# IN14.net
KiCad netlist of a schematic drawn in Altium Designer
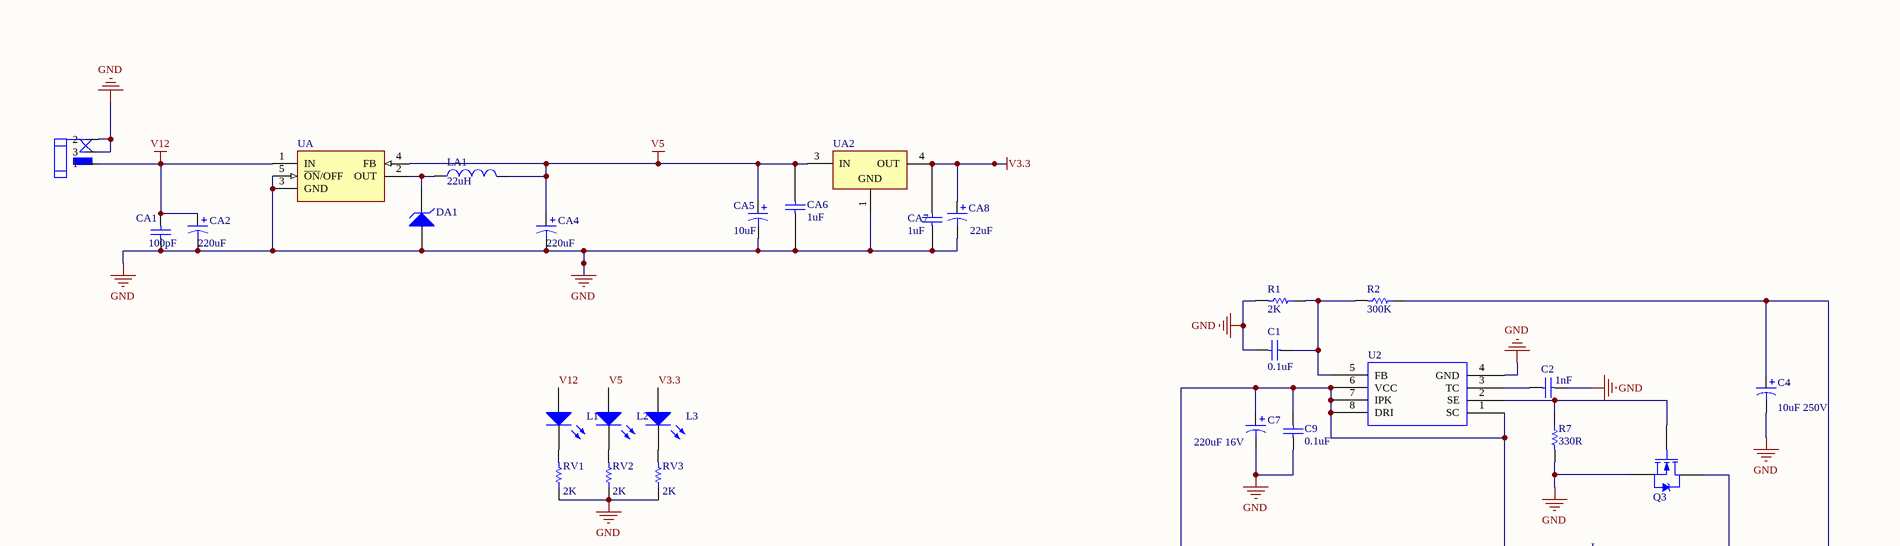
[diagram p0: IN14.SchDoc, top left]
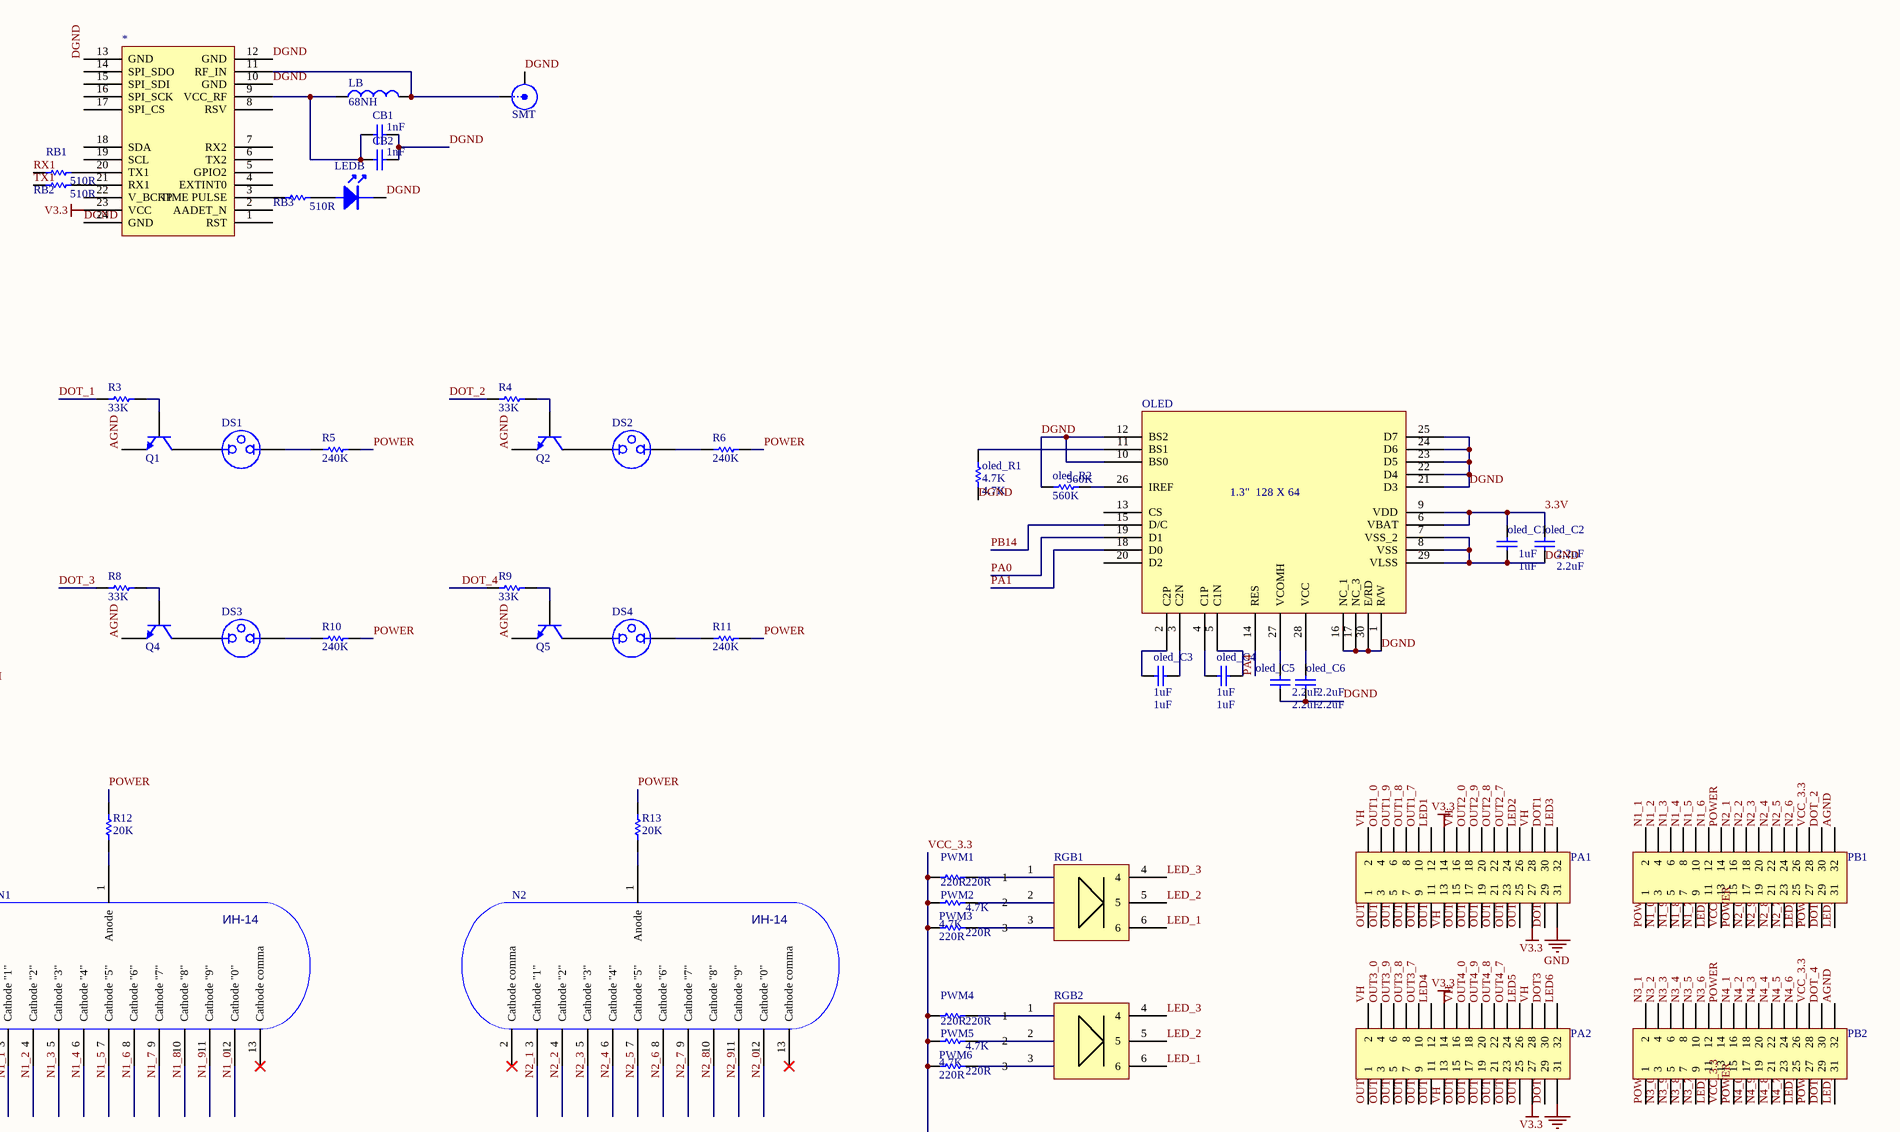
[diagram p1: IN14.SchDoc, top right]
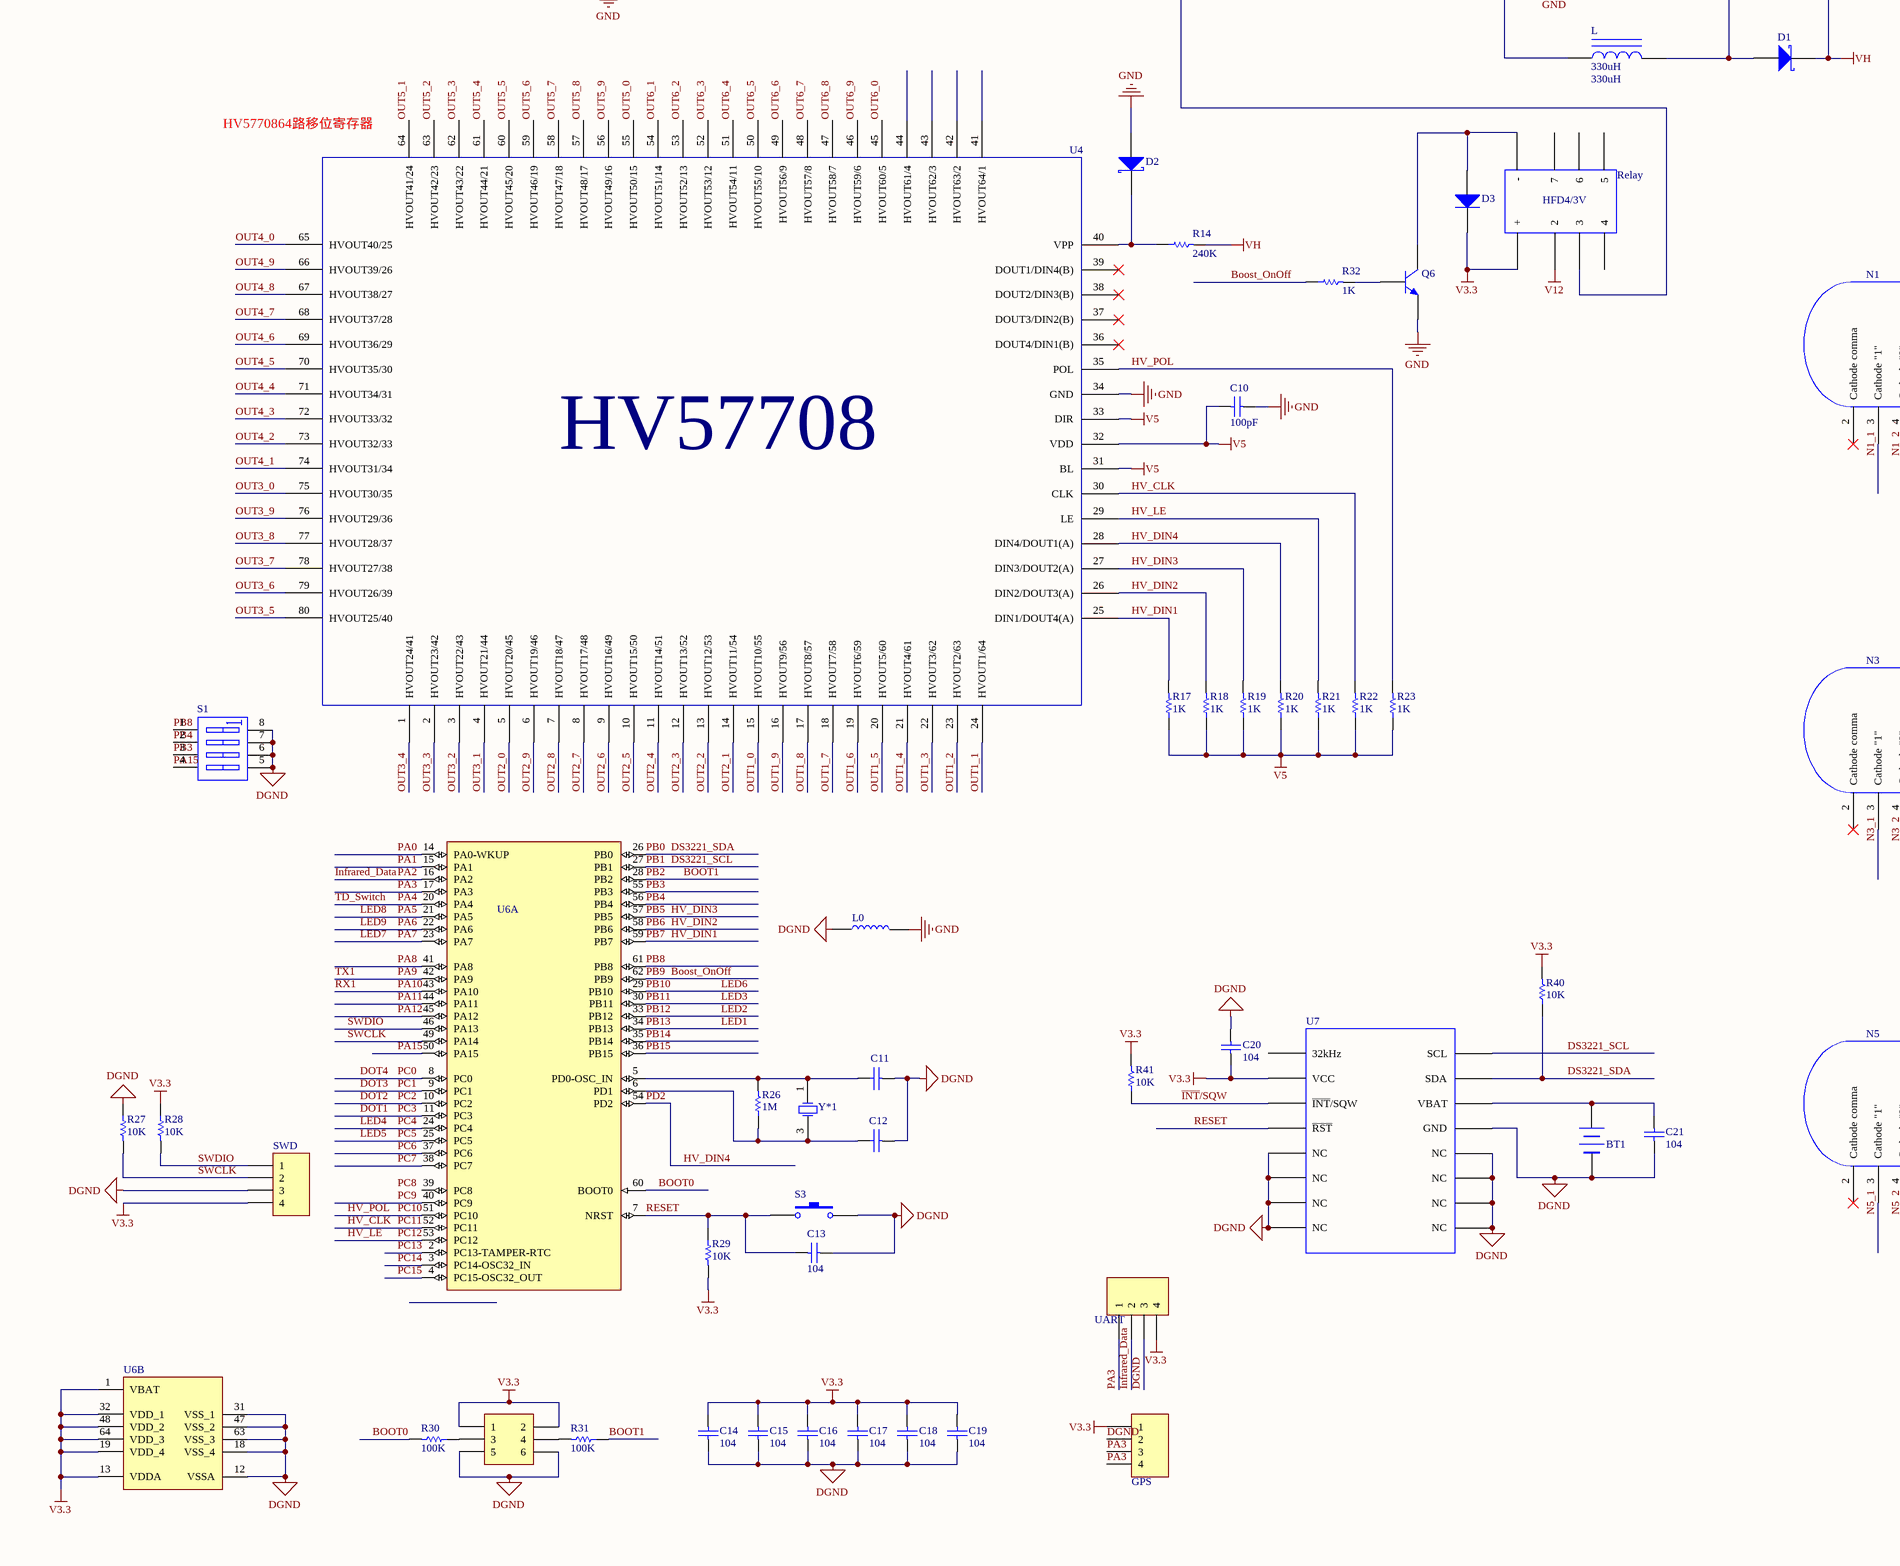
[diagram p2: IN14.SchDoc, bottom left]
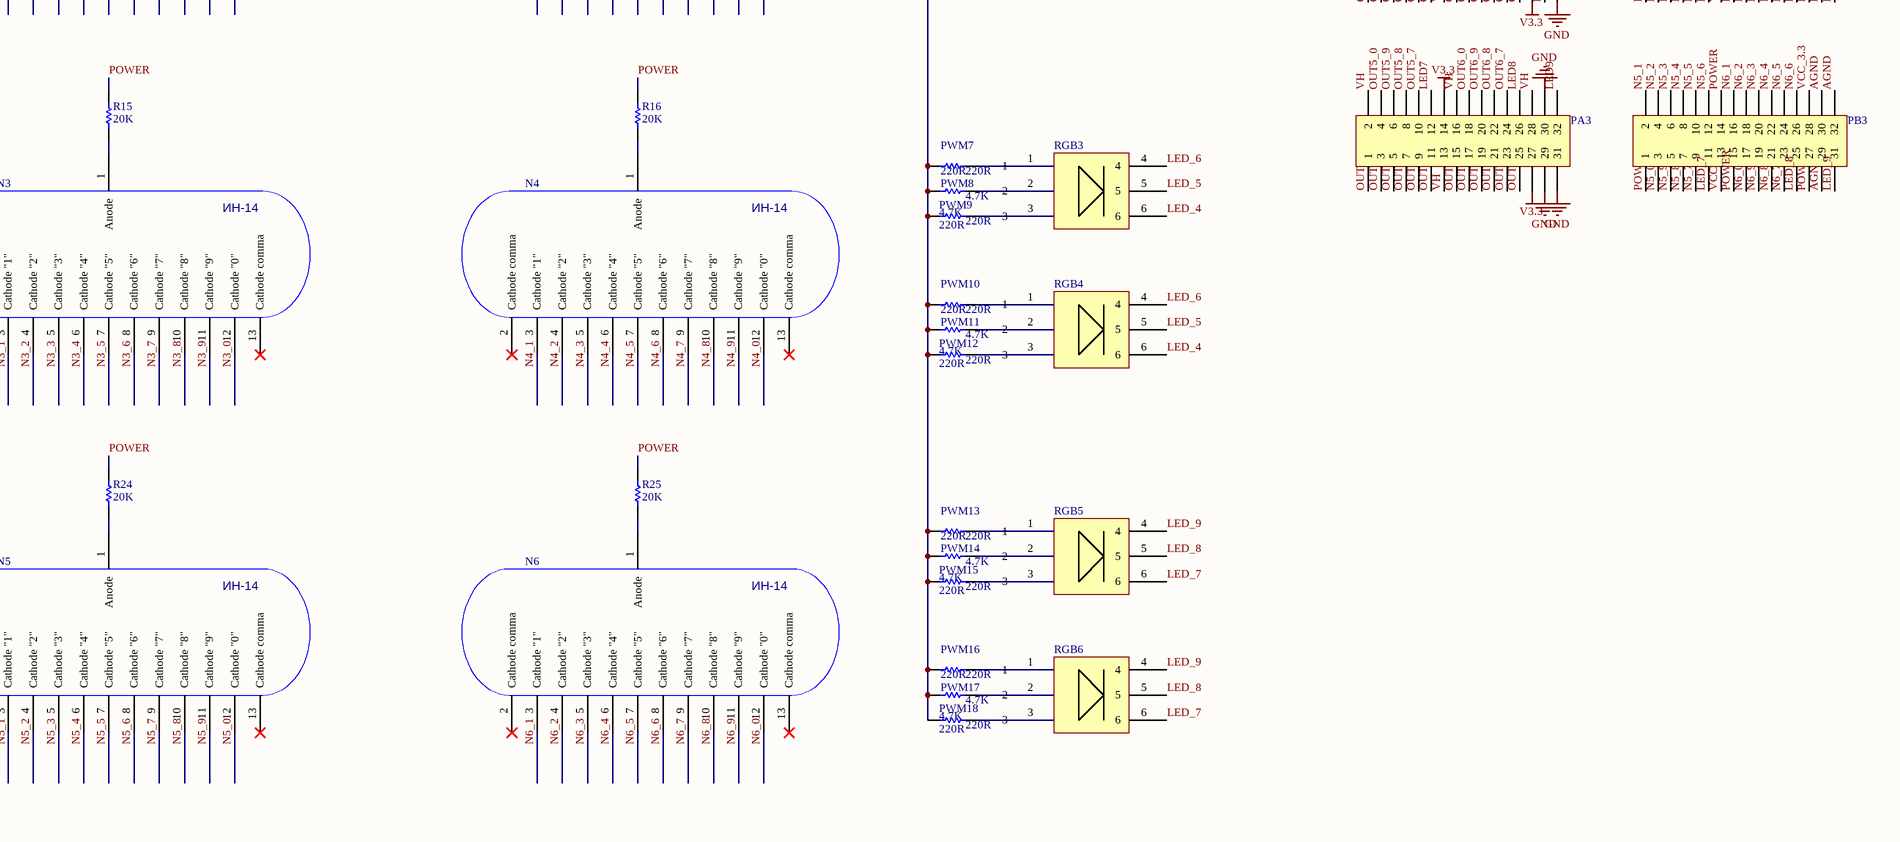
[diagram p3: IN14.SchDoc, bottom right]

(export (version "E")
  (design (tool "Eeschema 10.0.6"))
  (components
    (comp (ref "*") (value "~") (footprint "UM220") (libsource (lib "UM220") (part "Component_1")))
    (comp (ref "BOOT")
      (value "~")
      (footprint "HDR2X3")
      (description "Header, 3-Pin, Dual row")
      (fields (field (name "PUBLISHER") "Altium Limited"))
      (libsource (lib "Miscellaneous Connectors") (part "Header 3X2"))
    )
    (comp (ref "BT1") (value "~") (footprint "BAT1220") (libsource (lib "何龙华") (part "BATTERY")))
    (comp (ref "C1")
      (value "0.1uF")
      (footprint "C0603")
      (description "Capacitor (Semiconductor SIM Model)")
      (fields (field (name "PUBLISHER") "Altium Limited"))
      (libsource (lib "何龙华") (part "Cap Semi"))
    )
    (comp (ref "C2")
      (value "1nF")
      (footprint "C0603")
      (description "Capacitor (Semiconductor SIM Model)")
      (fields (field (name "PUBLISHER") "Altium Limited"))
      (libsource (lib "何龙华") (part "Cap Semi"))
    )
    (comp (ref "C4")
      (value "10uF 250V")
      (footprint "电容卧放2.54mm-1")
      (description "Polarized Capacitor (Radial)")
      (fields (field (name "PUBLISHER") "Altium Limited"))
      (libsource (lib "Miscellaneous Devices") (part "Cap Pol1"))
    )
    (comp (ref "C7")
      (value "220uF 16V")
      (footprint "HONOR_63X77")
      (description "Polarized Capacitor (Radial)")
      (fields (field (name "PUBLISHER") "Altium Limited"))
      (libsource (lib "Miscellaneous Devices") (part "Cap Pol1"))
    )
    (comp (ref "C9")
      (value "0.1uF")
      (footprint "C0603")
      (description "Capacitor (Semiconductor SIM Model)")
      (fields (field (name "PUBLISHER") "Altium Limited"))
      (libsource (lib "何龙华") (part "Cap Semi"))
    )
    (comp (ref "C10")
      (value "100pF")
      (footprint "C0603")
      (description "Capacitor")
      (fields (field (name "PUBLISHER") "Altium Limited"))
      (libsource (lib "Miscellaneous Devices") (part "Cap"))
    )
    (comp (ref "C11")
      (value "~")
      (footprint "C0603")
      (description "Capacitor")
      (libsource (lib "电容") (part "普通电容"))
    )
    (comp (ref "C12")
      (value "~")
      (footprint "C0603")
      (description "Capacitor")
      (libsource (lib "电容") (part "普通电容"))
    )
    (comp (ref "C13")
      (value "104")
      (footprint "C0603")
      (description "Capacitor (Semiconductor SIM Model)")
      (fields (field (name "PUBLISHER") "Altium Limited"))
      (libsource (lib "何龙华") (part "Cap Semi"))
    )
    (comp (ref "C14")
      (value "104")
      (footprint "C0603")
      (description "Capacitor (Semiconductor SIM Model)")
      (fields (field (name "PUBLISHER") "Altium Limited"))
      (libsource (lib "何龙华") (part "Cap Semi"))
    )
    (comp (ref "C15")
      (value "104")
      (footprint "C0603")
      (description "Capacitor (Semiconductor SIM Model)")
      (fields (field (name "PUBLISHER") "Altium Limited"))
      (libsource (lib "何龙华") (part "Cap Semi"))
    )
    (comp (ref "C16")
      (value "104")
      (footprint "C0603")
      (description "Capacitor (Semiconductor SIM Model)")
      (fields (field (name "PUBLISHER") "Altium Limited"))
      (libsource (lib "何龙华") (part "Cap Semi"))
    )
    (comp (ref "C17")
      (value "104")
      (footprint "C0603")
      (description "Capacitor (Semiconductor SIM Model)")
      (fields (field (name "PUBLISHER") "Altium Limited"))
      (libsource (lib "何龙华") (part "Cap Semi"))
    )
    (comp (ref "C18")
      (value "104")
      (footprint "C0603")
      (description "Capacitor (Semiconductor SIM Model)")
      (fields (field (name "PUBLISHER") "Altium Limited"))
      (libsource (lib "何龙华") (part "Cap Semi"))
    )
    (comp (ref "C19")
      (value "104")
      (footprint "C0603")
      (description "Capacitor (Semiconductor SIM Model)")
      (fields (field (name "PUBLISHER") "Altium Limited"))
      (libsource (lib "何龙华") (part "Cap Semi"))
    )
    (comp (ref "C20")
      (value "104")
      (footprint "C0603")
      (description "Capacitor (Semiconductor SIM Model)")
      (fields (field (name "PUBLISHER") "Altium Limited"))
      (libsource (lib "何龙华") (part "Cap Semi"))
    )
    (comp (ref "C21")
      (value "104")
      (footprint "C0603")
      (description "Capacitor (Semiconductor SIM Model)")
      (fields (field (name "PUBLISHER") "Altium Limited"))
      (libsource (lib "何龙华") (part "Cap Semi"))
    )
    (comp (ref "CA1")
      (value "100pF")
      (footprint "C0603")
      (description "Capacitor (Semiconductor SIM Model)")
      (fields (field (name "PUBLISHER") "Altium Limited"))
      (libsource (lib "Miscellaneous Devices") (part "Cap Semi"))
    )
    (comp (ref "CA2")
      (value "220uF")
      (footprint "CAP")
      (description "Polarized Capacitor (Surface Mount)")
      (fields (field (name "PUBLISHER") "Altium Limited"))
      (libsource (lib "Miscellaneous Devices") (part "Cap Pol3"))
    )
    (comp (ref "CA4")
      (value "220uF")
      (footprint "CAP")
      (description "Polarized Capacitor (Surface Mount)")
      (fields (field (name "PUBLISHER") "Altium Limited"))
      (libsource (lib "Miscellaneous Devices") (part "Cap Pol3"))
    )
    (comp (ref "CA5")
      (value "10uF")
      (footprint "3528")
      (description "Polarized Capacitor (Radial)")
      (fields (field (name "PUBLISHER") "Altium Limited"))
      (libsource (lib "Miscellaneous Devices") (part "Cap Pol1"))
    )
    (comp (ref "CA6")
      (value "1uF")
      (footprint "C0603")
      (description "Capacitor")
      (fields (field (name "PUBLISHER") "Altium Limited"))
      (libsource (lib "Miscellaneous Devices") (part "Cap"))
    )
    (comp (ref "CA7")
      (value "1uF")
      (footprint "C0603")
      (description "Capacitor")
      (fields (field (name "PUBLISHER") "Altium Limited"))
      (libsource (lib "Miscellaneous Devices") (part "Cap"))
    )
    (comp (ref "CA8")
      (value "22uF")
      (footprint "3528")
      (description "Polarized Capacitor (Radial)")
      (fields (field (name "PUBLISHER") "Altium Limited"))
      (libsource (lib "Miscellaneous Devices") (part "Cap Pol1"))
    )
    (comp (ref "CB1")
      (value "1nF")
      (footprint "C0603")
      (description "Capacitor (Semiconductor SIM Model)")
      (fields (field (name "PUBLISHER") "Altium Limited"))
      (libsource (lib "何龙华") (part "Cap Semi"))
    )
    (comp (ref "CB2")
      (value "1nF")
      (footprint "C0603")
      (description "Capacitor (Semiconductor SIM Model)")
      (fields (field (name "PUBLISHER") "Altium Limited"))
      (libsource (lib "何龙华") (part "Cap Semi"))
    )
    (comp (ref "D1")
      (value "~")
      (footprint "SMB")
      (description "Schottky Diode")
      (fields (field (name "PUBLISHER") "Altium Limited"))
      (libsource (lib "Miscellaneous Devices") (part "D Schottky"))
    )
    (comp (ref "D2")
      (value "~")
      (footprint "LL-34")
      (description "Schottky Rectifier")
      (fields (field (name "PUBLISHER") "Altium Limited"))
      (libsource (lib "Miscellaneous Devices") (part "Diode 11DQ03"))
    )
    (comp (ref "D3")
      (value "~")
      (footprint "1N4007W")
      (description "1 Amp General Purpose Rectifier")
      (fields (field (name "PUBLISHER") "Altium Limited"))
      (libsource (lib "Miscellaneous Devices") (part "Diode 1N4007"))
    )
    (comp (ref "DA1")
      (value "~")
      (footprint "3528")
      (description "Zener Diode")
      (fields (field (name "PUBLISHER") "Altium Limited"))
      (libsource (lib "Miscellaneous Devices") (part "D Zener"))
    )
    (comp (ref "DC1") (value "~") (footprint "DC-005") (libsource (lib "GBY的原理图库") (part "电源插座5.4mm")))
    (comp (ref "DS1")
      (value "~")
      (footprint "PIN2")
      (description "Neon Lamp")
      (fields (field (name "PUBLISHER") "Altium Limited"))
      (libsource (lib "Miscellaneous Devices") (part "Lamp Neon"))
    )
    (comp (ref "DS2")
      (value "~")
      (footprint "PIN2")
      (description "Neon Lamp")
      (fields (field (name "PUBLISHER") "Altium Limited"))
      (libsource (lib "Miscellaneous Devices") (part "Lamp Neon"))
    )
    (comp (ref "DS3")
      (value "~")
      (footprint "PIN2")
      (description "Neon Lamp")
      (fields (field (name "PUBLISHER") "Altium Limited"))
      (libsource (lib "Miscellaneous Devices") (part "Lamp Neon"))
    )
    (comp (ref "DS4")
      (value "~")
      (footprint "PIN2")
      (description "Neon Lamp")
      (fields (field (name "PUBLISHER") "Altium Limited"))
      (libsource (lib "Miscellaneous Devices") (part "Lamp Neon"))
    )
    (comp (ref "GPS")
      (value "Header 4")
      (footprint "HDR4X1_A")
      (description "接插件")
      (fields (field (name "PUBLISHER") "Altium Limited"))
      (libsource (lib "") (part "Header 4_1"))
    )
    (comp (ref "L")
      (value "330uH")
      (footprint "GDRH127")
      (description "Magnetic-Core Inductor")
      (fields (field (name "ALTIUM_VALUE") "330uH") (field (name "PUBLISHER") "Altium Limited"))
      (libsource (lib "Miscellaneous Devices") (part "Inductor Iron"))
    )
    (comp (ref "L0") (value "~") (footprint "0805") (libsource (lib "何龙华") (part "L0")))
    (comp (ref "L1")
      (value "~")
      (footprint "C0603")
      (description "Typical RED, GREEN, YELLOW, AMBER GaAs LED")
      (fields (field (name "PUBLISHER") "Altium Limited"))
      (libsource (lib "Miscellaneous Devices") (part "LED2"))
    )
    (comp (ref "L2")
      (value "~")
      (footprint "C0603")
      (description "Typical RED, GREEN, YELLOW, AMBER GaAs LED")
      (fields (field (name "PUBLISHER") "Altium Limited"))
      (libsource (lib "Miscellaneous Devices") (part "LED2"))
    )
    (comp (ref "L3")
      (value "~")
      (footprint "C0603")
      (description "Typical RED, GREEN, YELLOW, AMBER GaAs LED")
      (fields (field (name "PUBLISHER") "Altium Limited"))
      (libsource (lib "Miscellaneous Devices") (part "LED2"))
    )
    (comp (ref "LA1")
      (value "22uH")
      (footprint "LL")
      (description "Inductor")
      (fields (field (name "PUBLISHER") "Altium Limited"))
      (libsource (lib "Miscellaneous Devices") (part "Inductor"))
    )
    (comp (ref "LB")
      (value "68NH")
      (footprint "0805")
      (description "Inductor")
      (fields (field (name "PUBLISHER") "Altium Limited"))
      (libsource (lib "Miscellaneous Devices") (part "Inductor"))
    )
    (comp (ref "LEDB")
      (value "~")
      (footprint "C0603")
      (description "LED发光管")
      (libsource (lib "GBY的原理图库") (part "LED"))
    )
    (comp (ref "N1") (value "~") (footprint "IN14") (libsource (lib "NIXIEClock_SCHLib") (part "ИН-14")))
    (comp (ref "N2") (value "~") (footprint "IN14") (libsource (lib "NIXIEClock_SCHLib") (part "ИН-14")))
    (comp (ref "N3") (value "~") (footprint "IN14") (libsource (lib "NIXIEClock_SCHLib") (part "ИН-14")))
    (comp (ref "N4") (value "~") (footprint "IN14") (libsource (lib "NIXIEClock_SCHLib") (part "ИН-14")))
    (comp (ref "N5") (value "~") (footprint "IN14") (libsource (lib "NIXIEClock_SCHLib") (part "ИН-14")))
    (comp (ref "N6") (value "~") (footprint "IN14") (libsource (lib "NIXIEClock_SCHLib") (part "ИН-14")))
    (comp (ref "OLED") (value "~") (footprint "OLED") (libsource (lib "四旋翼") (part "1.3 inch oled")))
    (comp (ref "oled_C1")
      (value "1uF")
      (footprint "C0603")
      (description "Capacitor")
      (fields (field (name "ALTIUM_VALUE") "1uF") (field (name "PUBLISHER") "Altium Limited"))
      (libsource (lib "Miscellaneous Devices") (part "Cap"))
    )
    (comp (ref "oled_C2")
      (value "2.2uF")
      (footprint "C0603")
      (description "Capacitor")
      (fields (field (name "ALTIUM_VALUE") "2.2uF") (field (name "PUBLISHER") "Altium Limited"))
      (libsource (lib "Miscellaneous Devices") (part "Cap"))
    )
    (comp (ref "oled_C3")
      (value "1uF")
      (footprint "C0603")
      (description "Capacitor")
      (fields (field (name "ALTIUM_VALUE") "1uF") (field (name "PUBLISHER") "Altium Limited"))
      (libsource (lib "Miscellaneous Devices") (part "Cap"))
    )
    (comp (ref "oled_C4")
      (value "1uF")
      (footprint "C0603")
      (description "Capacitor")
      (fields (field (name "ALTIUM_VALUE") "1uF") (field (name "PUBLISHER") "Altium Limited"))
      (libsource (lib "Miscellaneous Devices") (part "Cap"))
    )
    (comp (ref "oled_C5")
      (value "2.2uF")
      (footprint "C0603")
      (description "Capacitor")
      (fields (field (name "ALTIUM_VALUE") "2.2uF") (field (name "PUBLISHER") "Altium Limited"))
      (libsource (lib "Miscellaneous Devices") (part "Cap"))
    )
    (comp (ref "oled_C6")
      (value "2.2uF")
      (footprint "C0603")
      (description "Capacitor")
      (fields (field (name "ALTIUM_VALUE") "2.2uF") (field (name "PUBLISHER") "Altium Limited"))
      (libsource (lib "Miscellaneous Devices") (part "Cap"))
    )
    (comp (ref "oled_R1")
      (value "4.7K")
      (footprint "R0603")
      (description "Resistor")
      (fields (field (name "ALTIUM_VALUE") "4.7K") (field (name "PUBLISHER") "Altium Limited"))
      (libsource (lib "Miscellaneous Devices") (part "Res1"))
    )
    (comp (ref "oled_R2")
      (value "560K")
      (footprint "R0603")
      (description "Resistor")
      (fields (field (name "ALTIUM_VALUE") "560K") (field (name "PUBLISHER") "Altium Limited"))
      (libsource (lib "Miscellaneous Devices") (part "Res1"))
    )
    (comp (ref "PA1")
      (value "~")
      (footprint "HDR2X16")
      (description "Header, 16-Pin, Dual row")
      (fields (field (name "PUBLISHER") "Altium Limited"))
      (libsource (lib "Miscellaneous Connectors") (part "Header 16X2"))
    )
    (comp (ref "PA2")
      (value "~")
      (footprint "HDR2X16")
      (description "Header, 16-Pin, Dual row")
      (fields (field (name "PUBLISHER") "Altium Limited"))
      (libsource (lib "Miscellaneous Connectors") (part "Header 16X2"))
    )
    (comp (ref "PA3")
      (value "~")
      (footprint "HDR2X16")
      (description "Header, 16-Pin, Dual row")
      (fields (field (name "PUBLISHER") "Altium Limited"))
      (libsource (lib "Miscellaneous Connectors") (part "Header 16X2"))
    )
    (comp (ref "PB1")
      (value "~")
      (footprint "贴片32")
      (description "Header, 16-Pin, Dual row")
      (fields (field (name "PUBLISHER") "Altium Limited"))
      (libsource (lib "Miscellaneous Connectors") (part "Header 16X2"))
    )
    (comp (ref "PB2")
      (value "~")
      (footprint "贴片32")
      (description "Header, 16-Pin, Dual row")
      (fields (field (name "PUBLISHER") "Altium Limited"))
      (libsource (lib "Miscellaneous Connectors") (part "Header 16X2"))
    )
    (comp (ref "PB3")
      (value "~")
      (footprint "贴片32")
      (description "Header, 16-Pin, Dual row")
      (fields (field (name "PUBLISHER") "Altium Limited"))
      (libsource (lib "Miscellaneous Connectors") (part "Header 16X2"))
    )
    (comp (ref "PWM1")
      (value "220R")
      (footprint "R0603")
      (description "Resistor")
      (fields (field (name "ALTIUM_VALUE") "220R") (field (name "PUBLISHER") "Altium Limited"))
      (libsource (lib "Miscellaneous Devices") (part "Res1"))
    )
    (comp (ref "PWM2")
      (value "4.7K")
      (footprint "R0603")
      (description "Resistor")
      (fields (field (name "ALTIUM_VALUE") "4.7K") (field (name "PUBLISHER") "Altium Limited"))
      (libsource (lib "Miscellaneous Devices") (part "Res1"))
    )
    (comp (ref "PWM3")
      (value "220R")
      (footprint "R0603")
      (description "Resistor")
      (fields (field (name "ALTIUM_VALUE") "220R") (field (name "PUBLISHER") "Altium Limited"))
      (libsource (lib "Miscellaneous Devices") (part "Res1"))
    )
    (comp (ref "PWM4")
      (value "220R")
      (footprint "R0603")
      (description "Resistor")
      (fields (field (name "ALTIUM_VALUE") "220R") (field (name "PUBLISHER") "Altium Limited"))
      (libsource (lib "Miscellaneous Devices") (part "Res1"))
    )
    (comp (ref "PWM5")
      (value "4.7K")
      (footprint "R0603")
      (description "Resistor")
      (fields (field (name "ALTIUM_VALUE") "4.7K") (field (name "PUBLISHER") "Altium Limited"))
      (libsource (lib "Miscellaneous Devices") (part "Res1"))
    )
    (comp (ref "PWM6")
      (value "220R")
      (footprint "R0603")
      (description "Resistor")
      (fields (field (name "ALTIUM_VALUE") "220R") (field (name "PUBLISHER") "Altium Limited"))
      (libsource (lib "Miscellaneous Devices") (part "Res1"))
    )
    (comp (ref "PWM7")
      (value "220R")
      (footprint "R0603")
      (description "Resistor")
      (fields (field (name "ALTIUM_VALUE") "220R") (field (name "PUBLISHER") "Altium Limited"))
      (libsource (lib "Miscellaneous Devices") (part "Res1"))
    )
    (comp (ref "PWM8")
      (value "4.7K")
      (footprint "R0603")
      (description "Resistor")
      (fields (field (name "ALTIUM_VALUE") "4.7K") (field (name "PUBLISHER") "Altium Limited"))
      (libsource (lib "Miscellaneous Devices") (part "Res1"))
    )
    (comp (ref "PWM9")
      (value "220R")
      (footprint "R0603")
      (description "Resistor")
      (fields (field (name "ALTIUM_VALUE") "220R") (field (name "PUBLISHER") "Altium Limited"))
      (libsource (lib "Miscellaneous Devices") (part "Res1"))
    )
    (comp (ref "PWM10")
      (value "220R")
      (footprint "R0603")
      (description "Resistor")
      (fields (field (name "ALTIUM_VALUE") "220R") (field (name "PUBLISHER") "Altium Limited"))
      (libsource (lib "Miscellaneous Devices") (part "Res1"))
    )
    (comp (ref "PWM11")
      (value "4.7K")
      (footprint "R0603")
      (description "Resistor")
      (fields (field (name "ALTIUM_VALUE") "4.7K") (field (name "PUBLISHER") "Altium Limited"))
      (libsource (lib "Miscellaneous Devices") (part "Res1"))
    )
    (comp (ref "PWM12")
      (value "220R")
      (footprint "R0603")
      (description "Resistor")
      (fields (field (name "ALTIUM_VALUE") "220R") (field (name "PUBLISHER") "Altium Limited"))
      (libsource (lib "Miscellaneous Devices") (part "Res1"))
    )
    (comp (ref "PWM13")
      (value "220R")
      (footprint "R0603")
      (description "Resistor")
      (fields (field (name "ALTIUM_VALUE") "220R") (field (name "PUBLISHER") "Altium Limited"))
      (libsource (lib "Miscellaneous Devices") (part "Res1"))
    )
    (comp (ref "PWM14")
      (value "4.7K")
      (footprint "R0603")
      (description "Resistor")
      (fields (field (name "ALTIUM_VALUE") "4.7K") (field (name "PUBLISHER") "Altium Limited"))
      (libsource (lib "Miscellaneous Devices") (part "Res1"))
    )
    (comp (ref "PWM15")
      (value "220R")
      (footprint "R0603")
      (description "Resistor")
      (fields (field (name "ALTIUM_VALUE") "220R") (field (name "PUBLISHER") "Altium Limited"))
      (libsource (lib "Miscellaneous Devices") (part "Res1"))
    )
    (comp (ref "PWM16")
      (value "220R")
      (footprint "R0603")
      (description "Resistor")
      (fields (field (name "ALTIUM_VALUE") "220R") (field (name "PUBLISHER") "Altium Limited"))
      (libsource (lib "Miscellaneous Devices") (part "Res1"))
    )
    (comp (ref "PWM17")
      (value "4.7K")
      (footprint "R0603")
      (description "Resistor")
      (fields (field (name "ALTIUM_VALUE") "4.7K") (field (name "PUBLISHER") "Altium Limited"))
      (libsource (lib "Miscellaneous Devices") (part "Res1"))
    )
    (comp (ref "PWM18")
      (value "220R")
      (footprint "R0603")
      (description "Resistor")
      (fields (field (name "ALTIUM_VALUE") "220R") (field (name "PUBLISHER") "Altium Limited"))
      (libsource (lib "Miscellaneous Devices") (part "Res1"))
    )
    (comp (ref "Q1")
      (value "~")
      (footprint "SOT-23-3L")
      (description "NPN Bipolar Transistor")
      (fields (field (name "PUBLISHER") "Altium Limited"))
      (libsource (lib "何龙华") (part "NPN"))
    )
    (comp (ref "Q2")
      (value "~")
      (footprint "SOT-23-3L")
      (description "NPN Bipolar Transistor")
      (fields (field (name "PUBLISHER") "Altium Limited"))
      (libsource (lib "何龙华") (part "NPN"))
    )
    (comp (ref "Q3")
      (value "~")
      (footprint "TO-263-2L")
      (description "N-Channel Power MOSFET")
      (fields (field (name "PUBLISHER") "Altium Limited"))
      (libsource (lib "Miscellaneous Devices") (part "NMOS-2"))
    )
    (comp (ref "Q4")
      (value "~")
      (footprint "SOT-23-3L")
      (description "NPN Bipolar Transistor")
      (fields (field (name "PUBLISHER") "Altium Limited"))
      (libsource (lib "何龙华") (part "NPN"))
    )
    (comp (ref "Q5")
      (value "~")
      (footprint "SOT-23-3L")
      (description "NPN Bipolar Transistor")
      (fields (field (name "PUBLISHER") "Altium Limited"))
      (libsource (lib "何龙华") (part "NPN"))
    )
    (comp (ref "Q6")
      (value "~")
      (footprint "SOT-323")
      (description "NPN Bipolar Transistor")
      (fields (field (name "PUBLISHER") "Altium Limited"))
      (libsource (lib "何龙华") (part "NPN"))
    )
    (comp (ref "R1")
      (value "2K")
      (footprint "R0603")
      (description "Semiconductor Resistor")
      (fields (field (name "PUBLISHER") "Altium Limited"))
      (libsource (lib "何龙华") (part "Res Semi"))
    )
    (comp (ref "R2")
      (value "300K")
      (footprint "R0603")
      (description "Semiconductor Resistor")
      (fields (field (name "PUBLISHER") "Altium Limited"))
      (libsource (lib "何龙华") (part "Res Semi"))
    )
    (comp (ref "R3")
      (value "33K")
      (footprint "R0603")
      (description "Semiconductor Resistor")
      (fields (field (name "PUBLISHER") "Altium Limited"))
      (libsource (lib "何龙华") (part "Res Semi"))
    )
    (comp (ref "R4")
      (value "33K")
      (footprint "R0603")
      (description "Semiconductor Resistor")
      (fields (field (name "PUBLISHER") "Altium Limited"))
      (libsource (lib "何龙华") (part "Res Semi"))
    )
    (comp (ref "R5")
      (value "240K")
      (footprint "R0603")
      (description "Semiconductor Resistor")
      (fields (field (name "PUBLISHER") "Altium Limited"))
      (libsource (lib "何龙华") (part "Res Semi"))
    )
    (comp (ref "R6")
      (value "240K")
      (footprint "R0603")
      (description "Semiconductor Resistor")
      (fields (field (name "PUBLISHER") "Altium Limited"))
      (libsource (lib "何龙华") (part "Res Semi"))
    )
    (comp (ref "R7")
      (value "330R")
      (footprint "R0603")
      (description "Semiconductor Resistor")
      (fields (field (name "Comment") "330") (field (name "PUBLISHER") "Altium Limited"))
      (libsource (lib "何龙华") (part "Res Semi"))
    )
    (comp (ref "R8")
      (value "33K")
      (footprint "R0603")
      (description "Semiconductor Resistor")
      (fields (field (name "PUBLISHER") "Altium Limited"))
      (libsource (lib "何龙华") (part "Res Semi"))
    )
    (comp (ref "R9")
      (value "33K")
      (footprint "R0603")
      (description "Semiconductor Resistor")
      (fields (field (name "PUBLISHER") "Altium Limited"))
      (libsource (lib "何龙华") (part "Res Semi"))
    )
    (comp (ref "R10")
      (value "240K")
      (footprint "R0603")
      (description "Semiconductor Resistor")
      (fields (field (name "PUBLISHER") "Altium Limited"))
      (libsource (lib "何龙华") (part "Res Semi"))
    )
    (comp (ref "R11")
      (value "240K")
      (footprint "R0603")
      (description "Semiconductor Resistor")
      (fields (field (name "PUBLISHER") "Altium Limited"))
      (libsource (lib "何龙华") (part "Res Semi"))
    )
    (comp (ref "R12")
      (value "20K")
      (footprint "R0603")
      (description "Semiconductor Resistor")
      (fields (field (name "PUBLISHER") "Altium Limited"))
      (libsource (lib "何龙华") (part "Res Semi"))
    )
    (comp (ref "R13")
      (value "20K")
      (footprint "R0603")
      (description "Semiconductor Resistor")
      (fields (field (name "PUBLISHER") "Altium Limited"))
      (libsource (lib "何龙华") (part "Res Semi"))
    )
    (comp (ref "R14")
      (value "240K")
      (footprint "R0603")
      (description "Semiconductor Resistor")
      (fields (field (name "PUBLISHER") "Altium Limited"))
      (libsource (lib "何龙华") (part "Res Semi"))
    )
    (comp (ref "R15")
      (value "20K")
      (footprint "R0603")
      (description "Semiconductor Resistor")
      (fields (field (name "PUBLISHER") "Altium Limited"))
      (libsource (lib "何龙华") (part "Res Semi"))
    )
    (comp (ref "R16")
      (value "20K")
      (footprint "R0603")
      (description "Semiconductor Resistor")
      (fields (field (name "PUBLISHER") "Altium Limited"))
      (libsource (lib "何龙华") (part "Res Semi"))
    )
    (comp (ref "R17")
      (value "1K")
      (footprint "R0603")
      (description "Semiconductor Resistor")
      (fields (field (name "PUBLISHER") "Altium Limited"))
      (libsource (lib "何龙华") (part "Res Semi"))
    )
    (comp (ref "R18")
      (value "1K")
      (footprint "R0603")
      (description "Semiconductor Resistor")
      (fields (field (name "PUBLISHER") "Altium Limited"))
      (libsource (lib "何龙华") (part "Res Semi"))
    )
    (comp (ref "R19")
      (value "1K")
      (footprint "R0603")
      (description "Semiconductor Resistor")
      (fields (field (name "PUBLISHER") "Altium Limited"))
      (libsource (lib "何龙华") (part "Res Semi"))
    )
    (comp (ref "R20")
      (value "1K")
      (footprint "R0603")
      (description "Semiconductor Resistor")
      (fields (field (name "PUBLISHER") "Altium Limited"))
      (libsource (lib "何龙华") (part "Res Semi"))
    )
    (comp (ref "R21")
      (value "1K")
      (footprint "R0603")
      (description "Semiconductor Resistor")
      (fields (field (name "PUBLISHER") "Altium Limited"))
      (libsource (lib "何龙华") (part "Res Semi"))
    )
    (comp (ref "R22")
      (value "1K")
      (footprint "R0603")
      (description "Semiconductor Resistor")
      (fields (field (name "PUBLISHER") "Altium Limited"))
      (libsource (lib "何龙华") (part "Res Semi"))
    )
    (comp (ref "R23")
      (value "1K")
      (footprint "R0603")
      (description "Semiconductor Resistor")
      (fields (field (name "PUBLISHER") "Altium Limited"))
      (libsource (lib "何龙华") (part "Res Semi"))
    )
    (comp (ref "R24")
      (value "20K")
      (footprint "R0603")
      (description "Semiconductor Resistor")
      (fields (field (name "PUBLISHER") "Altium Limited"))
      (libsource (lib "何龙华") (part "Res Semi"))
    )
    (comp (ref "R25")
      (value "20K")
      (footprint "R0603")
      (description "Semiconductor Resistor")
      (fields (field (name "PUBLISHER") "Altium Limited"))
      (libsource (lib "何龙华") (part "Res Semi"))
    )
    (comp (ref "R26")
      (value "1M")
      (footprint "R0603")
      (description "Semiconductor Resistor")
      (fields (field (name "PUBLISHER") "Altium Limited"))
      (libsource (lib "何龙华") (part "Res Semi"))
    )
    (comp (ref "R27")
      (value "10K")
      (footprint "R0603")
      (description "Semiconductor Resistor")
      (fields (field (name "PUBLISHER") "Altium Limited"))
      (libsource (lib "何龙华") (part "Res Semi"))
    )
    (comp (ref "R28")
      (value "10K")
      (footprint "R0603")
      (description "Semiconductor Resistor")
      (fields (field (name "PUBLISHER") "Altium Limited"))
      (libsource (lib "何龙华") (part "Res Semi"))
    )
    (comp (ref "R29")
      (value "10K")
      (footprint "R0603")
      (description "Semiconductor Resistor")
      (fields (field (name "PUBLISHER") "Altium Limited"))
      (libsource (lib "何龙华") (part "Res Semi"))
    )
    (comp (ref "R30")
      (value "100K")
      (footprint "R0603")
      (description "Semiconductor Resistor")
      (fields (field (name "PUBLISHER") "Altium Limited"))
      (libsource (lib "何龙华") (part "Res Semi"))
    )
    (comp (ref "R31")
      (value "100K")
      (footprint "R0603")
      (description "Semiconductor Resistor")
      (fields (field (name "PUBLISHER") "Altium Limited"))
      (libsource (lib "何龙华") (part "Res Semi"))
    )
    (comp (ref "R32")
      (value "1K")
      (footprint "R0603")
      (description "Semiconductor Resistor")
      (fields (field (name "PUBLISHER") "Altium Limited"))
      (libsource (lib "何龙华") (part "Res Semi"))
    )
    (comp (ref "R40")
      (value "10K")
      (footprint "R0603")
      (description "Semiconductor Resistor")
      (fields (field (name "PUBLISHER") "Altium Limited"))
      (libsource (lib "何龙华") (part "Res Semi"))
    )
    (comp (ref "R41")
      (value "10K")
      (footprint "R0603")
      (description "Semiconductor Resistor")
      (fields (field (name "PUBLISHER") "Altium Limited"))
      (libsource (lib "何龙华") (part "Res Semi"))
    )
    (comp (ref "RB1")
      (value "510R")
      (footprint "R0603")
      (description "Semiconductor Resistor")
      (fields (field (name "PUBLISHER") "Altium Limited"))
      (libsource (lib "何龙华") (part "Res Semi"))
    )
    (comp (ref "RB2")
      (value "510R")
      (footprint "R0603")
      (description "Semiconductor Resistor")
      (fields (field (name "PUBLISHER") "Altium Limited"))
      (libsource (lib "何龙华") (part "Res Semi"))
    )
    (comp (ref "RB3")
      (value "510R")
      (footprint "R0603")
      (description "Semiconductor Resistor")
      (fields (field (name "PUBLISHER") "Altium Limited"))
      (libsource (lib "何龙华") (part "Res Semi"))
    )
    (comp (ref "Relay") (value "~") (footprint "HFD4") (libsource (lib "NIXIEClock") (part "Relay")))
    (comp (ref "RGB1") (value "~") (footprint "二极管5050") (libsource (lib "Schlib1") (part "Component_1")))
    (comp (ref "RGB2") (value "~") (footprint "二极管5050") (libsource (lib "Schlib1") (part "Component_1")))
    (comp (ref "RGB3") (value "~") (footprint "二极管5050") (libsource (lib "Schlib1") (part "Component_1")))
    (comp (ref "RGB4") (value "~") (footprint "二极管5050") (libsource (lib "Schlib1") (part "Component_1")))
    (comp (ref "RGB5") (value "~") (footprint "二极管5050") (libsource (lib "Schlib1") (part "Component_1")))
    (comp (ref "RGB6") (value "~") (footprint "二极管5050") (libsource (lib "Schlib1") (part "Component_1")))
    (comp (ref "RV1")
      (value "2K")
      (footprint "C0603")
      (description "Semiconductor Resistor")
      (fields (field (name "PUBLISHER") "Altium Limited"))
      (libsource (lib "Miscellaneous Devices") (part "Res Semi"))
    )
    (comp (ref "RV2")
      (value "2K")
      (footprint "C0603")
      (description "Semiconductor Resistor")
      (fields (field (name "PUBLISHER") "Altium Limited"))
      (libsource (lib "Miscellaneous Devices") (part "Res Semi"))
    )
    (comp (ref "RV3")
      (value "2K")
      (footprint "C0603")
      (description "Semiconductor Resistor")
      (fields (field (name "PUBLISHER") "Altium Limited"))
      (libsource (lib "Miscellaneous Devices") (part "Res Semi"))
    )
    (comp (ref "S1")
      (value "~")
      (footprint "dip8")
      (description "DIP Switch, 4 Position, SPST")
      (fields (field (name "PUBLISHER") "Altium Limited"))
      (libsource (lib "Miscellaneous Devices") (part "SW DIP-4"))
    )
    (comp (ref "S3")
      (value "~")
      (footprint "贴片按键（红头）")
      (description "Switch")
      (fields (field (name "PUBLISHER") "Altium Limited"))
      (libsource (lib "何龙华") (part "SW-PB"))
    )
    (comp (ref "SMT")
      (value "~")
      (footprint "SMB_V-RJ45")
      (description "SMB Straight Connector")
      (fields (field (name "PUBLISHER") "Altium Limited"))
      (libsource (lib "Miscellaneous Connectors") (part "SMB"))
    )
    (comp (ref "SWD")
      (value "~")
      (footprint "HDR1X4")
      (description "Header, 4-Pin")
      (fields (field (name "PUBLISHER") "Altium Limited"))
      (libsource (lib "Miscellaneous Connectors") (part "Header 4"))
    )
    (comp (ref "U2") (value "~") (footprint "SOIC8") (libsource (lib "NIXIEClock_SCHLib") (part "MC34063A")))
    (comp (ref "U4")
      (value "~")
      (footprint "HV57708PG")
      (libsource (lib "NIXIEClock_SCHLib") (part "HV57708"))
    )
    (comp (ref "U6")
      (value "~")
      (footprint "LQFP64_N")
      (libsource (lib "STMicroelectronics STM32 F1") (part "STM32F103RBT6"))
    )
    (comp (ref "U7") (value "~") (footprint "SOP16_75MM") (libsource (lib "NIXIEClock") (part "DS3231")))
    (comp (ref "UA")
      (value "~")
      (footprint "TO-263-5")
      (description "5V稳压芯片")
      (fields (field (name "PUBLISHER") "Altium Limited"))
      (libsource (lib "Fszhang") (part "LM2596T-5.0"))
    )
    (comp (ref "UA2")
      (value "~")
      (footprint "SOT223_N")
      (description "800mA Low-Dropout Linear Regulator")
      (fields
        (field (name "PARTNUMBER") "LM1117DT-3.3")
        (field (name "MANUFACTURER") "National Semiconductor")
        (field (name "PUBLISHER") "Altium Limited")
      )
      (libsource (lib "NSC LDO") (part "LM1117DT-3.3"))
    )
    (comp (ref "UART")
      (value "~")
      (footprint "HDR4X1_A")
      (description "接插件")
      (fields (field (name "PUBLISHER") "Altium Limited"))
      (libsource (lib "Fszhang") (part "Header 4"))
    )
    (comp (ref "Y*1")
      (value "~")
      (footprint "A3225")
      (description "Crystal Oscillator")
      (fields (field (name "PUBLISHER") "Altium Limited"))
      (libsource (lib "四旋翼") (part "XTAL(3225)"))
    )
  )
  (nets
    (net (code "1") (name "/3.3V") (class "Default")
      (node (ref "OLED") (pin "6") (pinfunction "VBAT_6") (pintype "passive"))
      (node (ref "OLED") (pin "9") (pinfunction "VDD_9") (pintype "passive"))
      (node (ref "oled_C1") (pin "2") (pinfunction "2_2") (pintype "passive"))
      (node (ref "oled_C2") (pin "2") (pinfunction "2_2") (pintype "passive"))
    )
    (net (code "2") (name "/AGND") (class "Default")
      (node (ref "PB1") (pin "32") (pinfunction "32_32") (pintype "passive"))
      (node (ref "PB2") (pin "32") (pinfunction "32_32") (pintype "passive"))
      (node (ref "PB3") (pin "29") (pinfunction "29_29") (pintype "passive"))
      (node (ref "PB3") (pin "30") (pinfunction "30_30") (pintype "passive"))
      (node (ref "PB3") (pin "32") (pinfunction "32_32") (pintype "passive"))
      (node (ref "Q1") (pin "2") (pinfunction "E_2") (pintype "passive"))
      (node (ref "Q2") (pin "2") (pinfunction "E_2") (pintype "passive"))
      (node (ref "Q4") (pin "2") (pinfunction "E_2") (pintype "passive"))
      (node (ref "Q5") (pin "2") (pinfunction "E_2") (pintype "passive"))
    )
    (net (code "3") (name "/BOOT0") (class "Default")
      (node (ref "R30") (pin "2") (pinfunction "2_2") (pintype "passive"))
      (node (ref "U6") (pin "60") (pinfunction "BOOT0_60") (pintype "input"))
    )
    (net (code "4") (name "/BOOT1") (class "Default")
      (node (ref "R31") (pin "1") (pinfunction "1_1") (pintype "passive"))
      (node (ref "U6") (pin "28") (pinfunction "PB2_28") (pintype "bidirectional"))
    )
    (net (code "5") (name "/Boost_OnOff") (class "Default")
      (node (ref "R32") (pin "1") (pinfunction "1_1") (pintype "passive"))
      (node (ref "U6") (pin "62") (pinfunction "PB9_62") (pintype "bidirectional"))
    )
    (net (code "6") (name "/DOT1") (class "Default")
      (node (ref "PA1") (pin "30") (pinfunction "30_30") (pintype "passive"))
      (node (ref "U6") (pin "11") (pinfunction "PC3_11") (pintype "bidirectional"))
    )
    (net (code "7") (name "/DOT2") (class "Default")
      (node (ref "PA1") (pin "29") (pinfunction "29_29") (pintype "passive"))
      (node (ref "U6") (pin "10") (pinfunction "PC2_10") (pintype "bidirectional"))
    )
    (net (code "8") (name "/DOT3") (class "Default")
      (node (ref "PA2") (pin "30") (pinfunction "30_30") (pintype "passive"))
      (node (ref "U6") (pin "9") (pinfunction "PC1_9") (pintype "bidirectional"))
    )
    (net (code "9") (name "/DOT4") (class "Default")
      (node (ref "PA2") (pin "29") (pinfunction "29_29") (pintype "passive"))
      (node (ref "U6") (pin "8") (pinfunction "PC0_8") (pintype "bidirectional"))
    )
    (net (code "10") (name "/DOT_1") (class "Default")
      (node (ref "PB1") (pin "29") (pinfunction "29_29") (pintype "passive"))
      (node (ref "R3") (pin "2") (pinfunction "2_2") (pintype "passive"))
    )
    (net (code "11") (name "/DOT_2") (class "Default")
      (node (ref "PB1") (pin "30") (pinfunction "30_30") (pintype "passive"))
      (node (ref "R4") (pin "2") (pinfunction "2_2") (pintype "passive"))
    )
    (net (code "12") (name "/DOT_3") (class "Default")
      (node (ref "PB2") (pin "29") (pinfunction "29_29") (pintype "passive"))
      (node (ref "R8") (pin "2") (pinfunction "2_2") (pintype "passive"))
    )
    (net (code "13") (name "/DOT_4") (class "Default")
      (node (ref "PB2") (pin "30") (pinfunction "30_30") (pintype "passive"))
      (node (ref "R9") (pin "2") (pinfunction "2_2") (pintype "passive"))
    )
    (net (code "14") (name "/DS3221_SCL") (class "Default")
      (node (ref "U6") (pin "27") (pinfunction "PB1_27") (pintype "bidirectional"))
      (node (ref "U7") (pin "16") (pinfunction "SCL_16") (pintype "passive"))
    )
    (net (code "15") (name "/DS3221_SDA") (class "Default")
      (node (ref "R40") (pin "1") (pinfunction "1_1") (pintype "passive"))
      (node (ref "U6") (pin "26") (pinfunction "PB0_26") (pintype "bidirectional"))
      (node (ref "U7") (pin "15") (pinfunction "SDA_15") (pintype "passive"))
    )
    (net (code "16") (name "/HV_CLK") (class "Default")
      (node (ref "R22") (pin "2") (pinfunction "2_2") (pintype "passive"))
      (node (ref "U4") (pin "30") (pinfunction "CLK_30") (pintype "passive"))
      (node (ref "U6") (pin "52") (pinfunction "PC11_52") (pintype "bidirectional"))
    )
    (net (code "17") (name "/HV_DIN1") (class "Default")
      (node (ref "R17") (pin "2") (pinfunction "2_2") (pintype "passive"))
      (node (ref "U4") (pin "25") (pinfunction "DIN1/DOUT4(A)_25") (pintype "passive"))
      (node (ref "U6") (pin "59") (pinfunction "PB7_59") (pintype "bidirectional"))
    )
    (net (code "18") (name "/HV_DIN2") (class "Default")
      (node (ref "R18") (pin "2") (pinfunction "2_2") (pintype "passive"))
      (node (ref "U4") (pin "26") (pinfunction "DIN2/DOUT3(A)_26") (pintype "passive"))
      (node (ref "U6") (pin "58") (pinfunction "PB6_58") (pintype "bidirectional"))
    )
    (net (code "19") (name "/HV_DIN3") (class "Default")
      (node (ref "R19") (pin "2") (pinfunction "2_2") (pintype "passive"))
      (node (ref "U4") (pin "27") (pinfunction "DIN3/DOUT2(A)_27") (pintype "passive"))
      (node (ref "U6") (pin "57") (pinfunction "PB5_57") (pintype "bidirectional"))
    )
    (net (code "20") (name "/HV_DIN4") (class "Default")
      (node (ref "R20") (pin "2") (pinfunction "2_2") (pintype "passive"))
      (node (ref "U4") (pin "28") (pinfunction "DIN4/DOUT1(A)_28") (pintype "passive"))
      (node (ref "U6") (pin "54") (pinfunction "PD2_54") (pintype "bidirectional"))
    )
    (net (code "21") (name "/HV_LE") (class "Default")
      (node (ref "R21") (pin "2") (pinfunction "2_2") (pintype "passive"))
      (node (ref "U4") (pin "29") (pinfunction "LE_29") (pintype "passive"))
      (node (ref "U6") (pin "53") (pinfunction "PC12_53") (pintype "bidirectional"))
    )
    (net (code "22") (name "/HV_POL") (class "Default")
      (node (ref "R23") (pin "2") (pinfunction "2_2") (pintype "passive"))
      (node (ref "U4") (pin "35") (pinfunction "POL_35") (pintype "passive"))
      (node (ref "U6") (pin "51") (pinfunction "PC10_51") (pintype "bidirectional"))
    )
    (net (code "23") (name "/Infrared_Data") (class "Default")
      (node (ref "U6") (pin "16") (pinfunction "PA2_16") (pintype "bidirectional"))
      (node (ref "UART") (pin "2") (pinfunction "2_2") (pintype "passive"))
    )
    (net (code "24") (name "/LED1") (class "Default")
      (node (ref "PA1") (pin "12") (pinfunction "12_12") (pintype "passive"))
      (node (ref "U6") (pin "34") (pinfunction "PB13_34") (pintype "bidirectional"))
    )
    (net (code "25") (name "/LED2") (class "Default")
      (node (ref "PA1") (pin "26") (pinfunction "26_26") (pintype "passive"))
      (node (ref "U6") (pin "33") (pinfunction "PB12_33") (pintype "bidirectional"))
    )
    (net (code "26") (name "/LED3") (class "Default")
      (node (ref "PA1") (pin "32") (pinfunction "32_32") (pintype "passive"))
      (node (ref "U6") (pin "30") (pinfunction "PB11_30") (pintype "bidirectional"))
    )
    (net (code "27") (name "/LED4") (class "Default")
      (node (ref "PA2") (pin "12") (pinfunction "12_12") (pintype "passive"))
      (node (ref "U6") (pin "24") (pinfunction "PC4_24") (pintype "bidirectional"))
    )
    (net (code "28") (name "/LED5") (class "Default")
      (node (ref "PA2") (pin "26") (pinfunction "26_26") (pintype "passive"))
      (node (ref "U6") (pin "25") (pinfunction "PC5_25") (pintype "bidirectional"))
    )
    (net (code "29") (name "/LED6") (class "Default")
      (node (ref "PA2") (pin "32") (pinfunction "32_32") (pintype "passive"))
      (node (ref "U6") (pin "29") (pinfunction "PB10_29") (pintype "bidirectional"))
    )
    (net (code "30") (name "/LED7") (class "Default")
      (node (ref "PA3") (pin "12") (pinfunction "12_12") (pintype "passive"))
      (node (ref "U6") (pin "23") (pinfunction "PA7_23") (pintype "bidirectional"))
    )
    (net (code "31") (name "/LED8") (class "Default")
      (node (ref "PA3") (pin "26") (pinfunction "26_26") (pintype "passive"))
      (node (ref "U6") (pin "21") (pinfunction "PA5_21") (pintype "bidirectional"))
    )
    (net (code "32") (name "/LED9") (class "Default")
      (node (ref "PA3") (pin "32") (pinfunction "32_32") (pintype "passive"))
      (node (ref "U6") (pin "22") (pinfunction "PA6_22") (pintype "bidirectional"))
    )
    (net (code "33") (name "/LED_1") (class "Default")
      (node (ref "PB1") (pin "11") (pinfunction "11_11") (pintype "passive"))
      (node (ref "RGB1") (pin "6") (pinfunction "6_6") (pintype "passive"))
      (node (ref "RGB2") (pin "6") (pinfunction "6_6") (pintype "passive"))
    )
    (net (code "34") (name "/LED_2") (class "Default")
      (node (ref "PB1") (pin "25") (pinfunction "25_25") (pintype "passive"))
      (node (ref "RGB1") (pin "5") (pinfunction "5_5") (pintype "passive"))
      (node (ref "RGB2") (pin "5") (pinfunction "5_5") (pintype "passive"))
    )
    (net (code "35") (name "/LED_3") (class "Default")
      (node (ref "PB1") (pin "31") (pinfunction "31_31") (pintype "passive"))
      (node (ref "RGB1") (pin "4") (pinfunction "4_4") (pintype "passive"))
      (node (ref "RGB2") (pin "4") (pinfunction "4_4") (pintype "passive"))
    )
    (net (code "36") (name "/LED_4") (class "Default")
      (node (ref "PB2") (pin "11") (pinfunction "11_11") (pintype "passive"))
      (node (ref "RGB3") (pin "6") (pinfunction "6_6") (pintype "passive"))
      (node (ref "RGB4") (pin "6") (pinfunction "6_6") (pintype "passive"))
    )
    (net (code "37") (name "/LED_5") (class "Default")
      (node (ref "PB2") (pin "25") (pinfunction "25_25") (pintype "passive"))
      (node (ref "RGB3") (pin "5") (pinfunction "5_5") (pintype "passive"))
      (node (ref "RGB4") (pin "5") (pinfunction "5_5") (pintype "passive"))
    )
    (net (code "38") (name "/LED_6") (class "Default")
      (node (ref "PB2") (pin "31") (pinfunction "31_31") (pintype "passive"))
      (node (ref "RGB3") (pin "4") (pinfunction "4_4") (pintype "passive"))
      (node (ref "RGB4") (pin "4") (pinfunction "4_4") (pintype "passive"))
    )
    (net (code "39") (name "/LED_7") (class "Default")
      (node (ref "PB3") (pin "11") (pinfunction "11_11") (pintype "passive"))
      (node (ref "RGB5") (pin "6") (pinfunction "6_6") (pintype "passive"))
      (node (ref "RGB6") (pin "6") (pinfunction "6_6") (pintype "passive"))
    )
    (net (code "40") (name "/LED_8") (class "Default")
      (node (ref "PB3") (pin "25") (pinfunction "25_25") (pintype "passive"))
      (node (ref "RGB5") (pin "5") (pinfunction "5_5") (pintype "passive"))
      (node (ref "RGB6") (pin "5") (pinfunction "5_5") (pintype "passive"))
    )
    (net (code "41") (name "/LED_9") (class "Default")
      (node (ref "PB3") (pin "31") (pinfunction "31_31") (pintype "passive"))
      (node (ref "RGB5") (pin "4") (pinfunction "4_4") (pintype "passive"))
      (node (ref "RGB6") (pin "4") (pinfunction "4_4") (pintype "passive"))
    )
    (net (code "42") (name "/N1_0") (class "Default")
      (node (ref "N1") (pin "12") (pinfunction "Cathode_\"0\"_12") (pintype "passive"))
      (node (ref "PB1") (pin "3") (pinfunction "3_3") (pintype "passive"))
    )
    (net (code "43") (name "/N1_1") (class "Default")
      (node (ref "N1") (pin "3") (pinfunction "Cathode_\"1\"_3") (pintype "passive"))
      (node (ref "PB1") (pin "2") (pinfunction "2_2") (pintype "passive"))
    )
    (net (code "44") (name "/N1_2") (class "Default")
      (node (ref "N1") (pin "4") (pinfunction "Cathode_\"2\"_4") (pintype "passive"))
      (node (ref "PB1") (pin "4") (pinfunction "4_4") (pintype "passive"))
    )
    (net (code "45") (name "/N1_3") (class "Default")
      (node (ref "N1") (pin "5") (pinfunction "Cathode_\"3\"_5") (pintype "passive"))
      (node (ref "PB1") (pin "6") (pinfunction "6_6") (pintype "passive"))
    )
    (net (code "46") (name "/N1_4") (class "Default")
      (node (ref "N1") (pin "6") (pinfunction "Cathode_\"4\"_6") (pintype "passive"))
      (node (ref "PB1") (pin "8") (pinfunction "8_8") (pintype "passive"))
    )
    (net (code "47") (name "/N1_5") (class "Default")
      (node (ref "N1") (pin "7") (pinfunction "Cathode_\"5\"_7") (pintype "passive"))
      (node (ref "PB1") (pin "10") (pinfunction "10_10") (pintype "passive"))
    )
    (net (code "48") (name "/N1_6") (class "Default")
      (node (ref "N1") (pin "8") (pinfunction "Cathode_\"6\"_8") (pintype "passive"))
      (node (ref "PB1") (pin "12") (pinfunction "12_12") (pintype "passive"))
    )
    (net (code "49") (name "/N1_7") (class "Default")
      (node (ref "N1") (pin "9") (pinfunction "Cathode_\"7\"_9") (pintype "passive"))
      (node (ref "PB1") (pin "9") (pinfunction "9_9") (pintype "passive"))
    )
    (net (code "50") (name "/N1_8") (class "Default")
      (node (ref "N1") (pin "10") (pinfunction "Cathode_\"8\"_10") (pintype "passive"))
      (node (ref "PB1") (pin "7") (pinfunction "7_7") (pintype "passive"))
    )
    (net (code "51") (name "/N1_9") (class "Default")
      (node (ref "N1") (pin "11") (pinfunction "Cathode_\"9\"_11") (pintype "passive"))
      (node (ref "PB1") (pin "5") (pinfunction "5_5") (pintype "passive"))
    )
    (net (code "52") (name "/N2_0") (class "Default")
      (node (ref "N2") (pin "12") (pinfunction "Cathode_\"0\"_12") (pintype "passive"))
      (node (ref "PB1") (pin "17") (pinfunction "17_17") (pintype "passive"))
    )
    (net (code "53") (name "/N2_1") (class "Default")
      (node (ref "N2") (pin "3") (pinfunction "Cathode_\"1\"_3") (pintype "passive"))
      (node (ref "PB1") (pin "16") (pinfunction "16_16") (pintype "passive"))
    )
    (net (code "54") (name "/N2_2") (class "Default")
      (node (ref "N2") (pin "4") (pinfunction "Cathode_\"2\"_4") (pintype "passive"))
      (node (ref "PB1") (pin "18") (pinfunction "18_18") (pintype "passive"))
    )
    (net (code "55") (name "/N2_3") (class "Default")
      (node (ref "N2") (pin "5") (pinfunction "Cathode_\"3\"_5") (pintype "passive"))
      (node (ref "PB1") (pin "20") (pinfunction "20_20") (pintype "passive"))
    )
    (net (code "56") (name "/N2_4") (class "Default")
      (node (ref "N2") (pin "6") (pinfunction "Cathode_\"4\"_6") (pintype "passive"))
      (node (ref "PB1") (pin "22") (pinfunction "22_22") (pintype "passive"))
    )
    (net (code "57") (name "/N2_5") (class "Default")
      (node (ref "N2") (pin "7") (pinfunction "Cathode_\"5\"_7") (pintype "passive"))
      (node (ref "PB1") (pin "24") (pinfunction "24_24") (pintype "passive"))
    )
    (net (code "58") (name "/N2_6") (class "Default")
      (node (ref "N2") (pin "8") (pinfunction "Cathode_\"6\"_8") (pintype "passive"))
      (node (ref "PB1") (pin "26") (pinfunction "26_26") (pintype "passive"))
    )
    (net (code "59") (name "/N2_7") (class "Default")
      (node (ref "N2") (pin "9") (pinfunction "Cathode_\"7\"_9") (pintype "passive"))
      (node (ref "PB1") (pin "23") (pinfunction "23_23") (pintype "passive"))
    )
    (net (code "60") (name "/N2_8") (class "Default")
      (node (ref "N2") (pin "10") (pinfunction "Cathode_\"8\"_10") (pintype "passive"))
      (node (ref "PB1") (pin "21") (pinfunction "21_21") (pintype "passive"))
    )
    (net (code "61") (name "/N2_9") (class "Default")
      (node (ref "N2") (pin "11") (pinfunction "Cathode_\"9\"_11") (pintype "passive"))
      (node (ref "PB1") (pin "19") (pinfunction "19_19") (pintype "passive"))
    )
    (net (code "62") (name "/N3_0") (class "Default")
      (node (ref "N3") (pin "12") (pinfunction "Cathode_\"0\"_12") (pintype "passive"))
      (node (ref "PB2") (pin "3") (pinfunction "3_3") (pintype "passive"))
    )
    (net (code "63") (name "/N3_1") (class "Default")
      (node (ref "N3") (pin "3") (pinfunction "Cathode_\"1\"_3") (pintype "passive"))
      (node (ref "PB2") (pin "2") (pinfunction "2_2") (pintype "passive"))
    )
    (net (code "64") (name "/N3_2") (class "Default")
      (node (ref "N3") (pin "4") (pinfunction "Cathode_\"2\"_4") (pintype "passive"))
      (node (ref "PB2") (pin "4") (pinfunction "4_4") (pintype "passive"))
    )
    (net (code "65") (name "/N3_3") (class "Default")
      (node (ref "N3") (pin "5") (pinfunction "Cathode_\"3\"_5") (pintype "passive"))
      (node (ref "PB2") (pin "6") (pinfunction "6_6") (pintype "passive"))
    )
    (net (code "66") (name "/N3_4") (class "Default")
      (node (ref "N3") (pin "6") (pinfunction "Cathode_\"4\"_6") (pintype "passive"))
      (node (ref "PB2") (pin "8") (pinfunction "8_8") (pintype "passive"))
    )
    (net (code "67") (name "/N3_5") (class "Default")
      (node (ref "N3") (pin "7") (pinfunction "Cathode_\"5\"_7") (pintype "passive"))
      (node (ref "PB2") (pin "10") (pinfunction "10_10") (pintype "passive"))
    )
    (net (code "68") (name "/N3_6") (class "Default")
      (node (ref "N3") (pin "8") (pinfunction "Cathode_\"6\"_8") (pintype "passive"))
      (node (ref "PB2") (pin "12") (pinfunction "12_12") (pintype "passive"))
    )
    (net (code "69") (name "/N3_7") (class "Default")
      (node (ref "N3") (pin "9") (pinfunction "Cathode_\"7\"_9") (pintype "passive"))
      (node (ref "PB2") (pin "9") (pinfunction "9_9") (pintype "passive"))
    )
    (net (code "70") (name "/N3_8") (class "Default")
      (node (ref "N3") (pin "10") (pinfunction "Cathode_\"8\"_10") (pintype "passive"))
      (node (ref "PB2") (pin "7") (pinfunction "7_7") (pintype "passive"))
    )
    (net (code "71") (name "/N3_9") (class "Default")
      (node (ref "N3") (pin "11") (pinfunction "Cathode_\"9\"_11") (pintype "passive"))
      (node (ref "PB2") (pin "5") (pinfunction "5_5") (pintype "passive"))
    )
    (net (code "72") (name "/N4_0") (class "Default")
      (node (ref "N4") (pin "12") (pinfunction "Cathode_\"0\"_12") (pintype "passive"))
      (node (ref "PB2") (pin "17") (pinfunction "17_17") (pintype "passive"))
    )
    (net (code "73") (name "/N4_1") (class "Default")
      (node (ref "N4") (pin "3") (pinfunction "Cathode_\"1\"_3") (pintype "passive"))
      (node (ref "PB2") (pin "16") (pinfunction "16_16") (pintype "passive"))
    )
    (net (code "74") (name "/N4_2") (class "Default")
      (node (ref "N4") (pin "4") (pinfunction "Cathode_\"2\"_4") (pintype "passive"))
      (node (ref "PB2") (pin "18") (pinfunction "18_18") (pintype "passive"))
    )
    (net (code "75") (name "/N4_3") (class "Default")
      (node (ref "N4") (pin "5") (pinfunction "Cathode_\"3\"_5") (pintype "passive"))
      (node (ref "PB2") (pin "20") (pinfunction "20_20") (pintype "passive"))
    )
    (net (code "76") (name "/N4_4") (class "Default")
      (node (ref "N4") (pin "6") (pinfunction "Cathode_\"4\"_6") (pintype "passive"))
      (node (ref "PB2") (pin "22") (pinfunction "22_22") (pintype "passive"))
    )
    (net (code "77") (name "/N4_5") (class "Default")
      (node (ref "N4") (pin "7") (pinfunction "Cathode_\"5\"_7") (pintype "passive"))
      (node (ref "PB2") (pin "24") (pinfunction "24_24") (pintype "passive"))
    )
    (net (code "78") (name "/N4_6") (class "Default")
      (node (ref "N4") (pin "8") (pinfunction "Cathode_\"6\"_8") (pintype "passive"))
      (node (ref "PB2") (pin "26") (pinfunction "26_26") (pintype "passive"))
    )
    (net (code "79") (name "/N4_7") (class "Default")
      (node (ref "N4") (pin "9") (pinfunction "Cathode_\"7\"_9") (pintype "passive"))
      (node (ref "PB2") (pin "23") (pinfunction "23_23") (pintype "passive"))
    )
    (net (code "80") (name "/N4_8") (class "Default")
      (node (ref "N4") (pin "10") (pinfunction "Cathode_\"8\"_10") (pintype "passive"))
      (node (ref "PB2") (pin "21") (pinfunction "21_21") (pintype "passive"))
    )
    (net (code "81") (name "/N4_9") (class "Default")
      (node (ref "N4") (pin "11") (pinfunction "Cathode_\"9\"_11") (pintype "passive"))
      (node (ref "PB2") (pin "19") (pinfunction "19_19") (pintype "passive"))
    )
    (net (code "82") (name "/N5_0") (class "Default")
      (node (ref "N5") (pin "12") (pinfunction "Cathode_\"0\"_12") (pintype "passive"))
      (node (ref "PB3") (pin "3") (pinfunction "3_3") (pintype "passive"))
    )
    (net (code "83") (name "/N5_1") (class "Default")
      (node (ref "N5") (pin "3") (pinfunction "Cathode_\"1\"_3") (pintype "passive"))
      (node (ref "PB3") (pin "2") (pinfunction "2_2") (pintype "passive"))
    )
    (net (code "84") (name "/N5_2") (class "Default")
      (node (ref "N5") (pin "4") (pinfunction "Cathode_\"2\"_4") (pintype "passive"))
      (node (ref "PB3") (pin "4") (pinfunction "4_4") (pintype "passive"))
    )
    (net (code "85") (name "/N5_3") (class "Default")
      (node (ref "N5") (pin "5") (pinfunction "Cathode_\"3\"_5") (pintype "passive"))
      (node (ref "PB3") (pin "6") (pinfunction "6_6") (pintype "passive"))
    )
    (net (code "86") (name "/N5_4") (class "Default")
      (node (ref "N5") (pin "6") (pinfunction "Cathode_\"4\"_6") (pintype "passive"))
      (node (ref "PB3") (pin "8") (pinfunction "8_8") (pintype "passive"))
    )
    (net (code "87") (name "/N5_5") (class "Default")
      (node (ref "N5") (pin "7") (pinfunction "Cathode_\"5\"_7") (pintype "passive"))
      (node (ref "PB3") (pin "10") (pinfunction "10_10") (pintype "passive"))
    )
    (net (code "88") (name "/N5_6") (class "Default")
      (node (ref "N5") (pin "8") (pinfunction "Cathode_\"6\"_8") (pintype "passive"))
      (node (ref "PB3") (pin "12") (pinfunction "12_12") (pintype "passive"))
    )
    (net (code "89") (name "/N5_7") (class "Default")
      (node (ref "N5") (pin "9") (pinfunction "Cathode_\"7\"_9") (pintype "passive"))
      (node (ref "PB3") (pin "9") (pinfunction "9_9") (pintype "passive"))
    )
    (net (code "90") (name "/N5_8") (class "Default")
      (node (ref "N5") (pin "10") (pinfunction "Cathode_\"8\"_10") (pintype "passive"))
      (node (ref "PB3") (pin "7") (pinfunction "7_7") (pintype "passive"))
    )
    (net (code "91") (name "/N5_9") (class "Default")
      (node (ref "N5") (pin "11") (pinfunction "Cathode_\"9\"_11") (pintype "passive"))
      (node (ref "PB3") (pin "5") (pinfunction "5_5") (pintype "passive"))
    )
    (net (code "92") (name "/N6_0") (class "Default")
      (node (ref "N6") (pin "12") (pinfunction "Cathode_\"0\"_12") (pintype "passive"))
      (node (ref "PB3") (pin "17") (pinfunction "17_17") (pintype "passive"))
    )
    (net (code "93") (name "/N6_1") (class "Default")
      (node (ref "N6") (pin "3") (pinfunction "Cathode_\"1\"_3") (pintype "passive"))
      (node (ref "PB3") (pin "16") (pinfunction "16_16") (pintype "passive"))
    )
    (net (code "94") (name "/N6_2") (class "Default")
      (node (ref "N6") (pin "4") (pinfunction "Cathode_\"2\"_4") (pintype "passive"))
      (node (ref "PB3") (pin "18") (pinfunction "18_18") (pintype "passive"))
    )
    (net (code "95") (name "/N6_3") (class "Default")
      (node (ref "N6") (pin "5") (pinfunction "Cathode_\"3\"_5") (pintype "passive"))
      (node (ref "PB3") (pin "20") (pinfunction "20_20") (pintype "passive"))
    )
    (net (code "96") (name "/N6_4") (class "Default")
      (node (ref "N6") (pin "6") (pinfunction "Cathode_\"4\"_6") (pintype "passive"))
      (node (ref "PB3") (pin "22") (pinfunction "22_22") (pintype "passive"))
    )
    (net (code "97") (name "/N6_5") (class "Default")
      (node (ref "N6") (pin "7") (pinfunction "Cathode_\"5\"_7") (pintype "passive"))
      (node (ref "PB3") (pin "24") (pinfunction "24_24") (pintype "passive"))
    )
    (net (code "98") (name "/N6_6") (class "Default")
      (node (ref "N6") (pin "8") (pinfunction "Cathode_\"6\"_8") (pintype "passive"))
      (node (ref "PB3") (pin "26") (pinfunction "26_26") (pintype "passive"))
    )
    (net (code "99") (name "/N6_7") (class "Default")
      (node (ref "N6") (pin "9") (pinfunction "Cathode_\"7\"_9") (pintype "passive"))
      (node (ref "PB3") (pin "23") (pinfunction "23_23") (pintype "passive"))
    )
    (net (code "100") (name "/N6_8") (class "Default")
      (node (ref "N6") (pin "10") (pinfunction "Cathode_\"8\"_10") (pintype "passive"))
      (node (ref "PB3") (pin "21") (pinfunction "21_21") (pintype "passive"))
    )
    (net (code "101") (name "/N6_9") (class "Default")
      (node (ref "N6") (pin "11") (pinfunction "Cathode_\"9\"_11") (pintype "passive"))
      (node (ref "PB3") (pin "19") (pinfunction "19_19") (pintype "passive"))
    )
    (net (code "102") (name "/OUT1_0") (class "Default")
      (node (ref "PA1") (pin "4") (pinfunction "4_4") (pintype "passive"))
      (node (ref "U4") (pin "15") (pinfunction "HVOUT10/55_15") (pintype "passive"))
    )
    (net (code "103") (name "/OUT1_1") (class "Default")
      (node (ref "PA1") (pin "1") (pinfunction "1_1") (pintype "passive"))
      (node (ref "U4") (pin "24") (pinfunction "HVOUT1/64_24") (pintype "passive"))
    )
    (net (code "104") (name "/OUT1_2") (class "Default")
      (node (ref "PA1") (pin "3") (pinfunction "3_3") (pintype "passive"))
      (node (ref "U4") (pin "23") (pinfunction "HVOUT2/63_23") (pintype "passive"))
    )
    (net (code "105") (name "/OUT1_3") (class "Default")
      (node (ref "PA1") (pin "5") (pinfunction "5_5") (pintype "passive"))
      (node (ref "U4") (pin "22") (pinfunction "HVOUT3/62_22") (pintype "passive"))
    )
    (net (code "106") (name "/OUT1_4") (class "Default")
      (node (ref "PA1") (pin "7") (pinfunction "7_7") (pintype "passive"))
      (node (ref "U4") (pin "21") (pinfunction "HVOUT4/61_21") (pintype "passive"))
    )
    (net (code "107") (name "/OUT1_5") (class "Default")
      (node (ref "PA1") (pin "9") (pinfunction "9_9") (pintype "passive"))
      (node (ref "U4") (pin "20") (pinfunction "HVOUT5/60_20") (pintype "passive"))
    )
    (net (code "108") (name "/OUT1_6") (class "Default")
      (node (ref "PA1") (pin "11") (pinfunction "11_11") (pintype "passive"))
      (node (ref "U4") (pin "19") (pinfunction "HVOUT6/59_19") (pintype "passive"))
    )
    (net (code "109") (name "/OUT1_7") (class "Default")
      (node (ref "PA1") (pin "10") (pinfunction "10_10") (pintype "passive"))
      (node (ref "U4") (pin "18") (pinfunction "HVOUT7/58_18") (pintype "passive"))
    )
    (net (code "110") (name "/OUT1_8") (class "Default")
      (node (ref "PA1") (pin "8") (pinfunction "8_8") (pintype "passive"))
      (node (ref "U4") (pin "17") (pinfunction "HVOUT8/57_17") (pintype "passive"))
    )
    (net (code "111") (name "/OUT1_9") (class "Default")
      (node (ref "PA1") (pin "6") (pinfunction "6_6") (pintype "passive"))
      (node (ref "U4") (pin "16") (pinfunction "HVOUT9/56_16") (pintype "passive"))
    )
    (net (code "112") (name "/OUT2_0") (class "Default")
      (node (ref "PA1") (pin "18") (pinfunction "18_18") (pintype "passive"))
      (node (ref "U4") (pin "5") (pinfunction "HVOUT20/45_5") (pintype "passive"))
    )
    (net (code "113") (name "/OUT2_1") (class "Default")
      (node (ref "PA1") (pin "15") (pinfunction "15_15") (pintype "passive"))
      (node (ref "U4") (pin "14") (pinfunction "HVOUT11/54_14") (pintype "passive"))
    )
    (net (code "114") (name "/OUT2_2") (class "Default")
      (node (ref "PA1") (pin "17") (pinfunction "17_17") (pintype "passive"))
      (node (ref "U4") (pin "13") (pinfunction "HVOUT12/53_13") (pintype "passive"))
    )
    (net (code "115") (name "/OUT2_3") (class "Default")
      (node (ref "PA1") (pin "19") (pinfunction "19_19") (pintype "passive"))
      (node (ref "U4") (pin "12") (pinfunction "HVOUT13/52_12") (pintype "passive"))
    )
    (net (code "116") (name "/OUT2_4") (class "Default")
      (node (ref "PA1") (pin "21") (pinfunction "21_21") (pintype "passive"))
      (node (ref "U4") (pin "11") (pinfunction "HVOUT14/51_11") (pintype "passive"))
    )
    (net (code "117") (name "/OUT2_5") (class "Default")
      (node (ref "PA1") (pin "23") (pinfunction "23_23") (pintype "passive"))
      (node (ref "U4") (pin "10") (pinfunction "HVOUT15/50_10") (pintype "passive"))
    )
    (net (code "118") (name "/OUT2_6") (class "Default")
      (node (ref "PA1") (pin "25") (pinfunction "25_25") (pintype "passive"))
      (node (ref "U4") (pin "9") (pinfunction "HVOUT16/49_9") (pintype "passive"))
    )
    (net (code "119") (name "/OUT2_7") (class "Default")
      (node (ref "PA1") (pin "24") (pinfunction "24_24") (pintype "passive"))
      (node (ref "U4") (pin "8") (pinfunction "HVOUT17/48_8") (pintype "passive"))
    )
    (net (code "120") (name "/OUT2_8") (class "Default")
      (node (ref "PA1") (pin "22") (pinfunction "22_22") (pintype "passive"))
      (node (ref "U4") (pin "7") (pinfunction "HVOUT18/47_7") (pintype "passive"))
    )
    (net (code "121") (name "/OUT2_9") (class "Default")
      (node (ref "PA1") (pin "20") (pinfunction "20_20") (pintype "passive"))
      (node (ref "U4") (pin "6") (pinfunction "HVOUT19/46_6") (pintype "passive"))
    )
    (net (code "122") (name "/OUT3_0") (class "Default")
      (node (ref "PA2") (pin "4") (pinfunction "4_4") (pintype "passive"))
      (node (ref "U4") (pin "75") (pinfunction "HVOUT30/35_75") (pintype "passive"))
    )
    (net (code "123") (name "/OUT3_1") (class "Default")
      (node (ref "PA2") (pin "1") (pinfunction "1_1") (pintype "passive"))
      (node (ref "U4") (pin "4") (pinfunction "HVOUT21/44_4") (pintype "passive"))
    )
    (net (code "124") (name "/OUT3_2") (class "Default")
      (node (ref "PA2") (pin "3") (pinfunction "3_3") (pintype "passive"))
      (node (ref "U4") (pin "3") (pinfunction "HVOUT22/43_3") (pintype "passive"))
    )
    (net (code "125") (name "/OUT3_3") (class "Default")
      (node (ref "PA2") (pin "5") (pinfunction "5_5") (pintype "passive"))
      (node (ref "U4") (pin "2") (pinfunction "HVOUT23/42_2") (pintype "passive"))
    )
    (net (code "126") (name "/OUT3_4") (class "Default")
      (node (ref "PA2") (pin "7") (pinfunction "7_7") (pintype "passive"))
      (node (ref "U4") (pin "1") (pinfunction "HVOUT24/41_1") (pintype "passive"))
    )
    (net (code "127") (name "/OUT3_5") (class "Default")
      (node (ref "PA2") (pin "9") (pinfunction "9_9") (pintype "passive"))
      (node (ref "U4") (pin "80") (pinfunction "HVOUT25/40_80") (pintype "passive"))
    )
    (net (code "128") (name "/OUT3_6") (class "Default")
      (node (ref "PA2") (pin "11") (pinfunction "11_11") (pintype "passive"))
      (node (ref "U4") (pin "79") (pinfunction "HVOUT26/39_79") (pintype "passive"))
    )
    (net (code "129") (name "/OUT3_7") (class "Default")
      (node (ref "PA2") (pin "10") (pinfunction "10_10") (pintype "passive"))
      (node (ref "U4") (pin "78") (pinfunction "HVOUT27/38_78") (pintype "passive"))
    )
    (net (code "130") (name "/OUT3_8") (class "Default")
      (node (ref "PA2") (pin "8") (pinfunction "8_8") (pintype "passive"))
      (node (ref "U4") (pin "77") (pinfunction "HVOUT28/37_77") (pintype "passive"))
    )
    (net (code "131") (name "/OUT3_9") (class "Default")
      (node (ref "PA2") (pin "6") (pinfunction "6_6") (pintype "passive"))
      (node (ref "U4") (pin "76") (pinfunction "HVOUT29/36_76") (pintype "passive"))
    )
    (net (code "132") (name "/OUT4_0") (class "Default")
      (node (ref "PA2") (pin "18") (pinfunction "18_18") (pintype "passive"))
      (node (ref "U4") (pin "65") (pinfunction "HVOUT40/25_65") (pintype "passive"))
    )
    (net (code "133") (name "/OUT4_1") (class "Default")
      (node (ref "PA2") (pin "15") (pinfunction "15_15") (pintype "passive"))
      (node (ref "U4") (pin "74") (pinfunction "HVOUT31/34_74") (pintype "passive"))
    )
    (net (code "134") (name "/OUT4_2") (class "Default")
      (node (ref "PA2") (pin "17") (pinfunction "17_17") (pintype "passive"))
      (node (ref "U4") (pin "73") (pinfunction "HVOUT32/33_73") (pintype "passive"))
    )
    (net (code "135") (name "/OUT4_3") (class "Default")
      (node (ref "PA2") (pin "19") (pinfunction "19_19") (pintype "passive"))
      (node (ref "U4") (pin "72") (pinfunction "HVOUT33/32_72") (pintype "passive"))
    )
    (net (code "136") (name "/OUT4_4") (class "Default")
      (node (ref "PA2") (pin "21") (pinfunction "21_21") (pintype "passive"))
      (node (ref "U4") (pin "71") (pinfunction "HVOUT34/31_71") (pintype "passive"))
    )
    (net (code "137") (name "/OUT4_5") (class "Default")
      (node (ref "PA2") (pin "23") (pinfunction "23_23") (pintype "passive"))
      (node (ref "U4") (pin "70") (pinfunction "HVOUT35/30_70") (pintype "passive"))
    )
    (net (code "138") (name "/OUT4_6") (class "Default")
      (node (ref "PA2") (pin "25") (pinfunction "25_25") (pintype "passive"))
      (node (ref "U4") (pin "69") (pinfunction "HVOUT36/29_69") (pintype "passive"))
    )
    (net (code "139") (name "/OUT4_7") (class "Default")
      (node (ref "PA2") (pin "24") (pinfunction "24_24") (pintype "passive"))
      (node (ref "U4") (pin "68") (pinfunction "HVOUT37/28_68") (pintype "passive"))
    )
    (net (code "140") (name "/OUT4_8") (class "Default")
      (node (ref "PA2") (pin "22") (pinfunction "22_22") (pintype "passive"))
      (node (ref "U4") (pin "67") (pinfunction "HVOUT38/27_67") (pintype "passive"))
    )
    (net (code "141") (name "/OUT4_9") (class "Default")
      (node (ref "PA2") (pin "20") (pinfunction "20_20") (pintype "passive"))
      (node (ref "U4") (pin "66") (pinfunction "HVOUT39/26_66") (pintype "passive"))
    )
    (net (code "142") (name "/OUT5_0") (class "Default")
      (node (ref "PA3") (pin "4") (pinfunction "4_4") (pintype "passive"))
      (node (ref "U4") (pin "55") (pinfunction "HVOUT50/15_55") (pintype "passive"))
    )
    (net (code "143") (name "/OUT5_1") (class "Default")
      (node (ref "PA3") (pin "1") (pinfunction "1_1") (pintype "passive"))
      (node (ref "U4") (pin "64") (pinfunction "HVOUT41/24_64") (pintype "passive"))
    )
    (net (code "144") (name "/OUT5_2") (class "Default")
      (node (ref "PA3") (pin "3") (pinfunction "3_3") (pintype "passive"))
      (node (ref "U4") (pin "63") (pinfunction "HVOUT42/23_63") (pintype "passive"))
    )
    (net (code "145") (name "/OUT5_3") (class "Default")
      (node (ref "PA3") (pin "5") (pinfunction "5_5") (pintype "passive"))
      (node (ref "U4") (pin "62") (pinfunction "HVOUT43/22_62") (pintype "passive"))
    )
    (net (code "146") (name "/OUT5_4") (class "Default")
      (node (ref "PA3") (pin "7") (pinfunction "7_7") (pintype "passive"))
      (node (ref "U4") (pin "61") (pinfunction "HVOUT44/21_61") (pintype "passive"))
    )
    (net (code "147") (name "/OUT5_5") (class "Default")
      (node (ref "PA3") (pin "9") (pinfunction "9_9") (pintype "passive"))
      (node (ref "U4") (pin "60") (pinfunction "HVOUT45/20_60") (pintype "passive"))
    )
    (net (code "148") (name "/OUT5_6") (class "Default")
      (node (ref "PA3") (pin "11") (pinfunction "11_11") (pintype "passive"))
      (node (ref "U4") (pin "59") (pinfunction "HVOUT46/19_59") (pintype "passive"))
    )
    (net (code "149") (name "/OUT5_7") (class "Default")
      (node (ref "PA3") (pin "10") (pinfunction "10_10") (pintype "passive"))
      (node (ref "U4") (pin "58") (pinfunction "HVOUT47/18_58") (pintype "passive"))
    )
    (net (code "150") (name "/OUT5_8") (class "Default")
      (node (ref "PA3") (pin "8") (pinfunction "8_8") (pintype "passive"))
      (node (ref "U4") (pin "57") (pinfunction "HVOUT48/17_57") (pintype "passive"))
    )
    (net (code "151") (name "/OUT5_9") (class "Default")
      (node (ref "PA3") (pin "6") (pinfunction "6_6") (pintype "passive"))
      (node (ref "U4") (pin "56") (pinfunction "HVOUT49/16_56") (pintype "passive"))
    )
    (net (code "152") (name "/OUT6_0") (class "Default")
      (node (ref "PA3") (pin "18") (pinfunction "18_18") (pintype "passive"))
      (node (ref "U4") (pin "45") (pinfunction "HVOUT60/5_45") (pintype "passive"))
    )
    (net (code "153") (name "/OUT6_1") (class "Default")
      (node (ref "PA3") (pin "15") (pinfunction "15_15") (pintype "passive"))
      (node (ref "U4") (pin "54") (pinfunction "HVOUT51/14_54") (pintype "passive"))
    )
    (net (code "154") (name "/OUT6_2") (class "Default")
      (node (ref "PA3") (pin "17") (pinfunction "17_17") (pintype "passive"))
      (node (ref "U4") (pin "53") (pinfunction "HVOUT52/13_53") (pintype "passive"))
    )
    (net (code "155") (name "/OUT6_3") (class "Default")
      (node (ref "PA3") (pin "19") (pinfunction "19_19") (pintype "passive"))
      (node (ref "U4") (pin "52") (pinfunction "HVOUT53/12_52") (pintype "passive"))
    )
    (net (code "156") (name "/OUT6_4") (class "Default")
      (node (ref "PA3") (pin "21") (pinfunction "21_21") (pintype "passive"))
      (node (ref "U4") (pin "51") (pinfunction "HVOUT54/11_51") (pintype "passive"))
    )
    (net (code "157") (name "/OUT6_5") (class "Default")
      (node (ref "PA3") (pin "23") (pinfunction "23_23") (pintype "passive"))
      (node (ref "U4") (pin "50") (pinfunction "HVOUT55/10_50") (pintype "passive"))
    )
    (net (code "158") (name "/OUT6_6") (class "Default")
      (node (ref "PA3") (pin "25") (pinfunction "25_25") (pintype "passive"))
      (node (ref "U4") (pin "49") (pinfunction "HVOUT56/9_49") (pintype "passive"))
    )
    (net (code "159") (name "/OUT6_7") (class "Default")
      (node (ref "PA3") (pin "24") (pinfunction "24_24") (pintype "passive"))
      (node (ref "U4") (pin "48") (pinfunction "HVOUT57/8_48") (pintype "passive"))
    )
    (net (code "160") (name "/OUT6_8") (class "Default")
      (node (ref "PA3") (pin "22") (pinfunction "22_22") (pintype "passive"))
      (node (ref "U4") (pin "47") (pinfunction "HVOUT58/7_47") (pintype "passive"))
    )
    (net (code "161") (name "/OUT6_9") (class "Default")
      (node (ref "PA3") (pin "20") (pinfunction "20_20") (pintype "passive"))
      (node (ref "U4") (pin "46") (pinfunction "HVOUT59/6_46") (pintype "passive"))
    )
    (net (code "162") (name "/PA0") (class "Default")
      (node (ref "OLED") (pin "19") (pinfunction "D1_19") (pintype "passive"))
      (node (ref "U6") (pin "14") (pinfunction "PA0-WKUP_14") (pintype "bidirectional"))
    )
    (net (code "163") (name "/PA1") (class "Default")
      (node (ref "OLED") (pin "18") (pinfunction "D0_18") (pintype "passive"))
      (node (ref "U6") (pin "15") (pinfunction "PA1_15") (pintype "bidirectional"))
    )
    (net (code "164") (name "/PA3") (class "Default")
      (node (ref "GPS") (pin "3") (pinfunction "3_3") (pintype "passive"))
      (node (ref "GPS") (pin "4") (pinfunction "4_4") (pintype "passive"))
      (node (ref "U6") (pin "17") (pinfunction "PA3_17") (pintype "bidirectional"))
      (node (ref "UART") (pin "1") (pinfunction "1_1") (pintype "passive"))
    )
    (net (code "165") (name "/PA4") (class "Default")
      (node (ref "OLED") (pin "14") (pinfunction "RES_14") (pintype "passive"))
      (node (ref "U6") (pin "20") (pinfunction "PA4_20") (pintype "bidirectional"))
    )
    (net (code "166") (name "/PA8") (class "Default")
      (node (ref "U6") (pin "41") (pinfunction "PA8_41") (pintype "bidirectional"))
    )
    (net (code "167") (name "/PA9") (class "Default")
      (node (ref "RB2") (pin "1") (pinfunction "1_1") (pintype "passive"))
      (node (ref "U6") (pin "42") (pinfunction "PA9_42") (pintype "bidirectional"))
    )
    (net (code "168") (name "/PA10") (class "Default")
      (node (ref "RB1") (pin "1") (pinfunction "1_1") (pintype "passive"))
      (node (ref "U6") (pin "43") (pinfunction "PA10_43") (pintype "bidirectional"))
    )
    (net (code "169") (name "/PA11") (class "Default")
      (node (ref "U6") (pin "44") (pinfunction "PA11_44") (pintype "bidirectional"))
    )
    (net (code "170") (name "/PA12") (class "Default")
      (node (ref "U6") (pin "45") (pinfunction "PA12_45") (pintype "bidirectional"))
    )
    (net (code "171") (name "/PA15") (class "Default")
      (node (ref "S1") (pin "4") (pinfunction "A4_4") (pintype "passive"))
      (node (ref "U6") (pin "50") (pinfunction "PA15_50") (pintype "bidirectional"))
    )
    (net (code "172") (name "/PB3") (class "Default")
      (node (ref "S1") (pin "3") (pinfunction "A3_3") (pintype "passive"))
      (node (ref "U6") (pin "55") (pinfunction "PB3_55") (pintype "bidirectional"))
    )
    (net (code "173") (name "/PB4") (class "Default")
      (node (ref "S1") (pin "2") (pinfunction "A2_2") (pintype "passive"))
      (node (ref "U6") (pin "56") (pinfunction "PB4_56") (pintype "bidirectional"))
    )
    (net (code "174") (name "/PB8") (class "Default")
      (node (ref "S1") (pin "1") (pinfunction "A1_1") (pintype "passive"))
      (node (ref "U6") (pin "61") (pinfunction "PB8_61") (pintype "bidirectional"))
    )
    (net (code "175") (name "/PB14") (class "Default")
      (node (ref "OLED") (pin "15") (pinfunction "D/C_15") (pintype "passive"))
      (node (ref "U6") (pin "35") (pinfunction "PB14_35") (pintype "bidirectional"))
    )
    (net (code "176") (name "/PB15") (class "Default")
      (node (ref "U6") (pin "36") (pinfunction "PB15_36") (pintype "bidirectional"))
    )
    (net (code "177") (name "/PC6") (class "Default")
      (node (ref "U6") (pin "37") (pinfunction "PC6_37") (pintype "bidirectional"))
    )
    (net (code "178") (name "/PC7") (class "Default")
      (node (ref "U6") (pin "38") (pinfunction "PC7_38") (pintype "bidirectional"))
    )
    (net (code "180") (name "/PC9") (class "Default")
      (node (ref "U6") (pin "40") (pinfunction "PC9_40") (pintype "bidirectional"))
    )
    (net (code "181") (name "/PC13") (class "Default")
      (node (ref "U6") (pin "2") (pinfunction "PC13-TAMPER-RTC_2") (pintype "bidirectional"))
    )
    (net (code "182") (name "/PC14") (class "Default")
      (node (ref "U6") (pin "3") (pinfunction "PC14-OSC32_IN_3") (pintype "bidirectional"))
    )
    (net (code "183") (name "/PC15") (class "Default")
      (node (ref "U6") (pin "4") (pinfunction "PC15-OSC32_OUT_4") (pintype "bidirectional"))
    )
    (net (code "184") (name "/POWER") (class "Default")
      (node (ref "PB1") (pin "1") (pinfunction "1_1") (pintype "passive"))
      (node (ref "PB1") (pin "14") (pinfunction "14_14") (pintype "passive"))
      (node (ref "PB1") (pin "15") (pinfunction "15_15") (pintype "passive"))
      (node (ref "PB1") (pin "27") (pinfunction "27_27") (pintype "passive"))
      (node (ref "PB2") (pin "1") (pinfunction "1_1") (pintype "passive"))
      (node (ref "PB2") (pin "14") (pinfunction "14_14") (pintype "passive"))
      (node (ref "PB2") (pin "15") (pinfunction "15_15") (pintype "passive"))
      (node (ref "PB2") (pin "27") (pinfunction "27_27") (pintype "passive"))
      (node (ref "PB3") (pin "1") (pinfunction "1_1") (pintype "passive"))
      (node (ref "PB3") (pin "14") (pinfunction "14_14") (pintype "passive"))
      (node (ref "PB3") (pin "15") (pinfunction "15_15") (pintype "passive"))
      (node (ref "PB3") (pin "27") (pinfunction "27_27") (pintype "passive"))
      (node (ref "R10") (pin "2") (pinfunction "2_2") (pintype "passive"))
      (node (ref "R11") (pin "2") (pinfunction "2_2") (pintype "passive"))
      (node (ref "R12") (pin "2") (pinfunction "2_2") (pintype "passive"))
      (node (ref "R13") (pin "2") (pinfunction "2_2") (pintype "passive"))
      (node (ref "R15") (pin "2") (pinfunction "2_2") (pintype "passive"))
      (node (ref "R16") (pin "2") (pinfunction "2_2") (pintype "passive"))
      (node (ref "R24") (pin "2") (pinfunction "2_2") (pintype "passive"))
      (node (ref "R25") (pin "2") (pinfunction "2_2") (pintype "passive"))
      (node (ref "R5") (pin "2") (pinfunction "2_2") (pintype "passive"))
      (node (ref "R6") (pin "2") (pinfunction "2_2") (pintype "passive"))
    )
    (net (code "185") (name "/RESET") (class "Default")
      (node (ref "C13") (pin "1") (pinfunction "1_1") (pintype "passive"))
      (node (ref "R29") (pin "1") (pinfunction "1_1") (pintype "passive"))
      (node (ref "S3") (pin "1") (pinfunction "1_1") (pintype "passive"))
      (node (ref "U6") (pin "7") (pinfunction "NRST_7") (pintype "bidirectional"))
      (node (ref "U7") (pin "4") (pinfunction "~{RST}_4") (pintype "passive"))
    )
    (net (code "186") (name "/SWCLK") (class "Default")
      (node (ref "R27") (pin "2") (pinfunction "2_2") (pintype "passive"))
      (node (ref "SWD") (pin "2") (pinfunction "2_2") (pintype "passive"))
      (node (ref "U6") (pin "49") (pinfunction "PA14_49") (pintype "bidirectional"))
    )
    (net (code "187") (name "/SWDIO") (class "Default")
      (node (ref "R28") (pin "2") (pinfunction "2_2") (pintype "passive"))
      (node (ref "SWD") (pin "1") (pinfunction "1_1") (pintype "passive"))
      (node (ref "U6") (pin "46") (pinfunction "PA13_46") (pintype "bidirectional"))
    )
    (net (code "188") (name "/VCC_3.3") (class "Default")
      (node (ref "PB1") (pin "13") (pinfunction "13_13") (pintype "passive"))
      (node (ref "PB1") (pin "28") (pinfunction "28_28") (pintype "passive"))
      (node (ref "PB2") (pin "13") (pinfunction "13_13") (pintype "passive"))
      (node (ref "PB2") (pin "28") (pinfunction "28_28") (pintype "passive"))
      (node (ref "PB3") (pin "13") (pinfunction "13_13") (pintype "passive"))
      (node (ref "PB3") (pin "28") (pinfunction "28_28") (pintype "passive"))
      (node (ref "PWM1") (pin "2") (pinfunction "2_2") (pintype "passive"))
      (node (ref "PWM10") (pin "2") (pinfunction "2_2") (pintype "passive"))
      (node (ref "PWM11") (pin "2") (pinfunction "2_2") (pintype "passive"))
      (node (ref "PWM12") (pin "2") (pinfunction "2_2") (pintype "passive"))
      (node (ref "PWM13") (pin "2") (pinfunction "2_2") (pintype "passive"))
      (node (ref "PWM14") (pin "2") (pinfunction "2_2") (pintype "passive"))
      (node (ref "PWM15") (pin "2") (pinfunction "2_2") (pintype "passive"))
      (node (ref "PWM16") (pin "2") (pinfunction "2_2") (pintype "passive"))
      (node (ref "PWM17") (pin "2") (pinfunction "2_2") (pintype "passive"))
      (node (ref "PWM18") (pin "2") (pinfunction "2_2") (pintype "passive"))
      (node (ref "PWM2") (pin "2") (pinfunction "2_2") (pintype "passive"))
      (node (ref "PWM3") (pin "2") (pinfunction "2_2") (pintype "passive"))
      (node (ref "PWM4") (pin "2") (pinfunction "2_2") (pintype "passive"))
      (node (ref "PWM5") (pin "2") (pinfunction "2_2") (pintype "passive"))
      (node (ref "PWM6") (pin "2") (pinfunction "2_2") (pintype "passive"))
      (node (ref "PWM7") (pin "2") (pinfunction "2_2") (pintype "passive"))
      (node (ref "PWM8") (pin "2") (pinfunction "2_2") (pintype "passive"))
      (node (ref "PWM9") (pin "2") (pinfunction "2_2") (pintype "passive"))
    )
    (net (code "189") (name "/~{INT}{slash}SQW") (class "Default")
      (node (ref "R41") (pin "1") (pinfunction "1_1") (pintype "passive"))
      (node (ref "U7") (pin "3") (pinfunction "~{INT}/SQW_3") (pintype "passive"))
    )
    (net (code "190") (name "DGND") (class "Default")
      (node (ref "*") (pin "10") (pinfunction "GND_10") (pintype "passive"))
      (node (ref "*") (pin "12") (pinfunction "GND_12") (pintype "passive"))
      (node (ref "*") (pin "13") (pinfunction "GND_13") (pintype "passive"))
      (node (ref "*") (pin "24") (pinfunction "GND_24") (pintype "passive"))
      (node (ref "BOOT") (pin "5") (pinfunction "5_5") (pintype "passive"))
      (node (ref "BOOT") (pin "6") (pinfunction "6_6") (pintype "passive"))
      (node (ref "BT1") (pin "2") (pinfunction "-_2") (pintype "passive"))
      (node (ref "C11") (pin "1") (pinfunction "1_1") (pintype "passive"))
      (node (ref "C12") (pin "1") (pinfunction "1_1") (pintype "passive"))
      (node (ref "C13") (pin "2") (pinfunction "2_2") (pintype "passive"))
      (node (ref "C14") (pin "1") (pinfunction "1_1") (pintype "passive"))
      (node (ref "C15") (pin "1") (pinfunction "1_1") (pintype "passive"))
      (node (ref "C16") (pin "1") (pinfunction "1_1") (pintype "passive"))
      (node (ref "C17") (pin "1") (pinfunction "1_1") (pintype "passive"))
      (node (ref "C18") (pin "1") (pinfunction "1_1") (pintype "passive"))
      (node (ref "C19") (pin "1") (pinfunction "1_1") (pintype "passive"))
      (node (ref "C20") (pin "2") (pinfunction "2_2") (pintype "passive"))
      (node (ref "C21") (pin "1") (pinfunction "1_1") (pintype "passive"))
      (node (ref "CB1") (pin "1") (pinfunction "1_1") (pintype "passive"))
      (node (ref "CB2") (pin "1") (pinfunction "1_1") (pintype "passive"))
      (node (ref "GPS") (pin "2") (pinfunction "2_2") (pintype "passive"))
      (node (ref "L0") (pin "1") (pinfunction "1_1") (pintype "passive"))
      (node (ref "LEDB") (pin "2") (pinfunction "2_2") (pintype "passive"))
      (node (ref "OLED") (pin "1") (pinfunction "R/W_1") (pintype "passive"))
      (node (ref "OLED") (pin "10") (pinfunction "BS0_10") (pintype "passive"))
      (node (ref "OLED") (pin "12") (pinfunction "BS2_12") (pintype "passive"))
      (node (ref "OLED") (pin "16") (pinfunction "NC_1_16") (pintype "passive"))
      (node (ref "OLED") (pin "17") (pinfunction "NC_3_17") (pintype "passive"))
      (node (ref "OLED") (pin "21") (pinfunction "D3_21") (pintype "passive"))
      (node (ref "OLED") (pin "22") (pinfunction "D4_22") (pintype "passive"))
      (node (ref "OLED") (pin "23") (pinfunction "D5_23") (pintype "passive"))
      (node (ref "OLED") (pin "24") (pinfunction "D6_24") (pintype "passive"))
      (node (ref "OLED") (pin "25") (pinfunction "D7_25") (pintype "passive"))
      (node (ref "OLED") (pin "29") (pinfunction "VLSS_29") (pintype "passive"))
      (node (ref "OLED") (pin "30") (pinfunction "E/RD_30") (pintype "passive"))
      (node (ref "OLED") (pin "7") (pinfunction "VSS_2_7") (pintype "passive"))
      (node (ref "OLED") (pin "8") (pinfunction "VSS_8") (pintype "passive"))
      (node (ref "R27") (pin "1") (pinfunction "1_1") (pintype "passive"))
      (node (ref "S1") (pin "5") (pinfunction "B4_5") (pintype "passive"))
      (node (ref "S1") (pin "6") (pinfunction "B3_6") (pintype "passive"))
      (node (ref "S1") (pin "7") (pinfunction "B2_7") (pintype "passive"))
      (node (ref "S1") (pin "8") (pinfunction "B1_8") (pintype "passive"))
      (node (ref "S3") (pin "2") (pinfunction "2_2") (pintype "passive"))
      (node (ref "SMT") (pin "2") (pinfunction "Y_2") (pintype "passive"))
      (node (ref "SWD") (pin "3") (pinfunction "3_3") (pintype "passive"))
      (node (ref "U6") (pin "12") (pinfunction "VSSA_12") (pintype "power_in"))
      (node (ref "U6") (pin "18") (pinfunction "VSS_4_18") (pintype "power_in"))
      (node (ref "U6") (pin "31") (pinfunction "VSS_1_31") (pintype "power_in"))
      (node (ref "U6") (pin "47") (pinfunction "VSS_2_47") (pintype "power_in"))
      (node (ref "U6") (pin "63") (pinfunction "VSS_3_63") (pintype "power_in"))
      (node (ref "U7") (pin "10") (pinfunction "NC_10") (pintype "passive"))
      (node (ref "U7") (pin "11") (pinfunction "NC_11") (pintype "passive"))
      (node (ref "U7") (pin "12") (pinfunction "NC_12") (pintype "passive"))
      (node (ref "U7") (pin "13") (pinfunction "GND_13") (pintype "passive"))
      (node (ref "U7") (pin "5") (pinfunction "NC_5") (pintype "passive"))
      (node (ref "U7") (pin "6") (pinfunction "NC_6") (pintype "passive"))
      (node (ref "U7") (pin "7") (pinfunction "NC_7") (pintype "passive"))
      (node (ref "U7") (pin "8") (pinfunction "NC_8") (pintype "passive"))
      (node (ref "U7") (pin "9") (pinfunction "NC_9") (pintype "passive"))
      (node (ref "UART") (pin "3") (pinfunction "3_3") (pintype "passive"))
      (node (ref "oled_C1") (pin "1") (pinfunction "1_1") (pintype "passive"))
      (node (ref "oled_C2") (pin "1") (pinfunction "1_1") (pintype "passive"))
      (node (ref "oled_C5") (pin "1") (pinfunction "1_1") (pintype "passive"))
      (node (ref "oled_C6") (pin "1") (pinfunction "1_1") (pintype "passive"))
      (node (ref "oled_R1") (pin "1") (pinfunction "1_1") (pintype "passive"))
      (node (ref "oled_R2") (pin "1") (pinfunction "1_1") (pintype "passive"))
    )
    (net (code "191") (name "GND") (class "Default")
      (node (ref "C1") (pin "2") (pinfunction "2_2") (pintype "passive"))
      (node (ref "C10") (pin "1") (pinfunction "1_1") (pintype "passive"))
      (node (ref "C2") (pin "1") (pinfunction "1_1") (pintype "passive"))
      (node (ref "C4") (pin "2") (pinfunction "2_2") (pintype "passive"))
      (node (ref "C7") (pin "2") (pinfunction "2_2") (pintype "passive"))
      (node (ref "C9") (pin "1") (pinfunction "1_1") (pintype "passive"))
      (node (ref "CA1") (pin "1") (pinfunction "1_1") (pintype "passive"))
      (node (ref "CA2") (pin "2") (pinfunction "2_2") (pintype "passive"))
      (node (ref "CA4") (pin "2") (pinfunction "2_2") (pintype "passive"))
      (node (ref "CA5") (pin "2") (pinfunction "2_2") (pintype "passive"))
      (node (ref "CA6") (pin "1") (pinfunction "1_1") (pintype "passive"))
      (node (ref "CA7") (pin "2") (pinfunction "2_2") (pintype "passive"))
      (node (ref "CA8") (pin "2") (pinfunction "2_2") (pintype "passive"))
      (node (ref "D2") (pin "1") (pinfunction "A_1") (pintype "passive"))
      (node (ref "DA1") (pin "1") (pinfunction "A_1") (pintype "passive"))
      (node (ref "DC1") (pin "2") (pinfunction "2_2") (pintype "passive"))
      (node (ref "DC1") (pin "3") (pinfunction "3_3") (pintype "passive"))
      (node (ref "L0") (pin "2") (pinfunction "2_2") (pintype "passive"))
      (node (ref "PA1") (pin "31") (pinfunction "31_31") (pintype "passive"))
      (node (ref "PA2") (pin "31") (pinfunction "31_31") (pintype "passive"))
      (node (ref "PA3") (pin "29") (pinfunction "29_29") (pintype "passive"))
      (node (ref "PA3") (pin "30") (pinfunction "30_30") (pintype "passive"))
      (node (ref "PA3") (pin "31") (pinfunction "31_31") (pintype "passive"))
      (node (ref "Q3") (pin "3") (pinfunction "S_3") (pintype "passive"))
      (node (ref "Q6") (pin "2") (pinfunction "E_2") (pintype "passive"))
      (node (ref "R1") (pin "2") (pinfunction "2_2") (pintype "passive"))
      (node (ref "R7") (pin "2") (pinfunction "2_2") (pintype "passive"))
      (node (ref "RV1") (pin "1") (pinfunction "1_1") (pintype "passive"))
      (node (ref "RV2") (pin "1") (pinfunction "1_1") (pintype "passive"))
      (node (ref "RV3") (pin "1") (pinfunction "1_1") (pintype "passive"))
      (node (ref "U2") (pin "4") (pinfunction "GND_4") (pintype "passive"))
      (node (ref "U4") (pin "34") (pinfunction "GND_34") (pintype "passive"))
      (node (ref "UA") (pin "3") (pinfunction "GND_3") (pintype "power_in"))
      (node (ref "UA") (pin "5") (pinfunction "~{ON}/OFF_5") (pintype "input"))
      (node (ref "UA2") (pin "1") (pinfunction "GND_1") (pintype "power_in"))
    )
    (net (code "192") (name "Net-(*-RF_IN)") (class "Default")
      (node (ref "*") (pin "11") (pinfunction "RF_IN_11") (pintype "passive"))
      (node (ref "LB") (pin "2") (pinfunction "2_2") (pintype "passive"))
      (node (ref "SMT") (pin "1") (pinfunction "X_1") (pintype "passive"))
    )
    (net (code "193") (name "Net-(*-RX1)") (class "Default")
      (node (ref "*") (pin "21") (pinfunction "RX1_21") (pintype "passive"))
      (node (ref "RB2") (pin "2") (pinfunction "2_2") (pintype "passive"))
    )
    (net (code "194") (name "Net-(*-TIME_PULSE)") (class "Default")
      (node (ref "*") (pin "3") (pinfunction "TIME_PULSE_3") (pintype "passive"))
      (node (ref "RB3") (pin "1") (pinfunction "1_1") (pintype "passive"))
    )
    (net (code "195") (name "Net-(*-TX1)") (class "Default")
      (node (ref "*") (pin "20") (pinfunction "TX1_20") (pintype "passive"))
      (node (ref "RB1") (pin "2") (pinfunction "2_2") (pintype "passive"))
    )
    (net (code "196") (name "Net-(*-VCC_RF)") (class "Default")
      (node (ref "*") (pin "9") (pinfunction "VCC_RF_9") (pintype "passive"))
      (node (ref "CB1") (pin "2") (pinfunction "2_2") (pintype "passive"))
      (node (ref "CB2") (pin "2") (pinfunction "2_2") (pintype "passive"))
      (node (ref "LB") (pin "1") (pinfunction "1_1") (pintype "passive"))
    )
    (net (code "197") (name "Net-(BOOT-Pad3)") (class "Default")
      (node (ref "BOOT") (pin "3") (pinfunction "3_3") (pintype "passive"))
      (node (ref "R30") (pin "1") (pinfunction "1_1") (pintype "passive"))
    )
    (net (code "198") (name "Net-(BOOT-Pad4)") (class "Default")
      (node (ref "BOOT") (pin "4") (pinfunction "4_4") (pintype "passive"))
      (node (ref "R31") (pin "2") (pinfunction "2_2") (pintype "passive"))
    )
    (net (code "199") (name "Net-(BT1-+)") (class "Default")
      (node (ref "BT1") (pin "1") (pinfunction "+_1") (pintype "passive"))
      (node (ref "C21") (pin "2") (pinfunction "2_2") (pintype "passive"))
      (node (ref "U7") (pin "14") (pinfunction "VBAT_14") (pintype "passive"))
    )
    (net (code "200") (name "Net-(D1-A)") (class "Default")
      (node (ref "D1") (pin "1") (pinfunction "A_1") (pintype "passive"))
      (node (ref "L") (pin "2") (pinfunction "2_2") (pintype "passive"))
      (node (ref "Q3") (pin "2") (pinfunction "D_2") (pintype "passive"))
    )
    (net (code "201") (name "Net-(D2-K)") (class "Default")
      (node (ref "D2") (pin "2") (pinfunction "K_2") (pintype "passive"))
      (node (ref "R14") (pin "1") (pinfunction "1_1") (pintype "passive"))
      (node (ref "U4") (pin "40") (pinfunction "VPP_40") (pintype "passive"))
    )
    (net (code "202") (name "Net-(D3-A)") (class "Default")
      (node (ref "D3") (pin "1") (pinfunction "A_1") (pintype "passive"))
      (node (ref "Q6") (pin "3") (pinfunction "C_3") (pintype "passive"))
      (node (ref "Relay") (pin "8") (pinfunction "-_8") (pintype "passive"))
    )
    (net (code "203") (name "Net-(DA1-K)") (class "Default")
      (node (ref "DA1") (pin "2") (pinfunction "K_2") (pintype "passive"))
      (node (ref "LA1") (pin "1") (pinfunction "1_1") (pintype "passive"))
      (node (ref "UA") (pin "2") (pinfunction "OUT_2") (pintype "power_in"))
    )
    (net (code "204") (name "Net-(DS1-Pad2)") (class "Default")
      (node (ref "DS1") (pin "2") (pinfunction "2_2") (pintype "passive"))
      (node (ref "R5") (pin "1") (pinfunction "1_1") (pintype "passive"))
    )
    (net (code "205") (name "Net-(DS2-Pad2)") (class "Default")
      (node (ref "DS2") (pin "2") (pinfunction "2_2") (pintype "passive"))
      (node (ref "R6") (pin "1") (pinfunction "1_1") (pintype "passive"))
    )
    (net (code "206") (name "Net-(DS3-Pad2)") (class "Default")
      (node (ref "DS3") (pin "2") (pinfunction "2_2") (pintype "passive"))
      (node (ref "R10") (pin "1") (pinfunction "1_1") (pintype "passive"))
    )
    (net (code "207") (name "Net-(DS4-Pad2)") (class "Default")
      (node (ref "DS4") (pin "2") (pinfunction "2_2") (pintype "passive"))
      (node (ref "R11") (pin "1") (pinfunction "1_1") (pintype "passive"))
    )
    (net (code "208") (name "Net-(L1-K)") (class "Default")
      (node (ref "L1") (pin "2") (pinfunction "K_2") (pintype "passive"))
      (node (ref "RV1") (pin "2") (pinfunction "2_2") (pintype "passive"))
    )
    (net (code "209") (name "Net-(L2-K)") (class "Default")
      (node (ref "L2") (pin "2") (pinfunction "K_2") (pintype "passive"))
      (node (ref "RV2") (pin "2") (pinfunction "2_2") (pintype "passive"))
    )
    (net (code "210") (name "Net-(L3-K)") (class "Default")
      (node (ref "L3") (pin "2") (pinfunction "K_2") (pintype "passive"))
      (node (ref "RV3") (pin "2") (pinfunction "2_2") (pintype "passive"))
    )
    (net (code "211") (name "Net-(LEDB-Pad1)") (class "Default")
      (node (ref "LEDB") (pin "1") (pinfunction "1_1") (pintype "passive"))
      (node (ref "RB3") (pin "2") (pinfunction "2_2") (pintype "passive"))
    )
    (net (code "212") (name "Net-(N1-Anode)") (class "Default")
      (node (ref "N1") (pin "1") (pinfunction "Anode_1") (pintype "passive"))
      (node (ref "R12") (pin "1") (pinfunction "1_1") (pintype "passive"))
    )
    (net (code "213") (name "Net-(N2-Anode)") (class "Default")
      (node (ref "N2") (pin "1") (pinfunction "Anode_1") (pintype "passive"))
      (node (ref "R13") (pin "1") (pinfunction "1_1") (pintype "passive"))
    )
    (net (code "214") (name "Net-(N3-Anode)") (class "Default")
      (node (ref "N3") (pin "1") (pinfunction "Anode_1") (pintype "passive"))
      (node (ref "R15") (pin "1") (pinfunction "1_1") (pintype "passive"))
    )
    (net (code "215") (name "Net-(N4-Anode)") (class "Default")
      (node (ref "N4") (pin "1") (pinfunction "Anode_1") (pintype "passive"))
      (node (ref "R16") (pin "1") (pinfunction "1_1") (pintype "passive"))
    )
    (net (code "216") (name "Net-(N5-Anode)") (class "Default")
      (node (ref "N5") (pin "1") (pinfunction "Anode_1") (pintype "passive"))
      (node (ref "R24") (pin "1") (pinfunction "1_1") (pintype "passive"))
    )
    (net (code "217") (name "Net-(N6-Anode)") (class "Default")
      (node (ref "N6") (pin "1") (pinfunction "Anode_1") (pintype "passive"))
      (node (ref "R25") (pin "1") (pinfunction "1_1") (pintype "passive"))
    )
    (net (code "218") (name "Net-(OLED-BS1)") (class "Default")
      (node (ref "OLED") (pin "11") (pinfunction "BS1_11") (pintype "passive"))
      (node (ref "oled_R1") (pin "2") (pinfunction "2_2") (pintype "passive"))
    )
    (net (code "219") (name "Net-(OLED-C1N)") (class "Default")
      (node (ref "OLED") (pin "5") (pinfunction "C1N_5") (pintype "passive"))
      (node (ref "oled_C4") (pin "2") (pinfunction "2_2") (pintype "passive"))
    )
    (net (code "220") (name "Net-(OLED-C1P)") (class "Default")
      (node (ref "OLED") (pin "4") (pinfunction "C1P_4") (pintype "passive"))
      (node (ref "oled_C4") (pin "1") (pinfunction "1_1") (pintype "passive"))
    )
    (net (code "221") (name "Net-(OLED-C2N)") (class "Default")
      (node (ref "OLED") (pin "3") (pinfunction "C2N_3") (pintype "passive"))
      (node (ref "oled_C3") (pin "2") (pinfunction "2_2") (pintype "passive"))
    )
    (net (code "222") (name "Net-(OLED-C2P)") (class "Default")
      (node (ref "OLED") (pin "2") (pinfunction "C2P_2") (pintype "passive"))
      (node (ref "oled_C3") (pin "1") (pinfunction "1_1") (pintype "passive"))
    )
    (net (code "223") (name "Net-(OLED-IREF)") (class "Default")
      (node (ref "OLED") (pin "26") (pinfunction "IREF_26") (pintype "passive"))
      (node (ref "oled_R2") (pin "2") (pinfunction "2_2") (pintype "passive"))
    )
    (net (code "224") (name "Net-(OLED-VCC)") (class "Default")
      (node (ref "OLED") (pin "28") (pinfunction "VCC_28") (pintype "passive"))
      (node (ref "oled_C6") (pin "2") (pinfunction "2_2") (pintype "passive"))
    )
    (net (code "225") (name "Net-(OLED-VCOMH)") (class "Default")
      (node (ref "OLED") (pin "27") (pinfunction "VCOMH_27") (pintype "passive"))
      (node (ref "oled_C5") (pin "2") (pinfunction "2_2") (pintype "passive"))
    )
    (net (code "226") (name "Net-(PWM1-Pad1)") (class "Default")
      (node (ref "PWM1") (pin "1") (pinfunction "1_1") (pintype "passive"))
      (node (ref "RGB1") (pin "1") (pinfunction "1_1") (pintype "passive"))
    )
    (net (code "227") (name "Net-(PWM2-Pad1)") (class "Default")
      (node (ref "PWM2") (pin "1") (pinfunction "1_1") (pintype "passive"))
      (node (ref "RGB1") (pin "2") (pinfunction "2_2") (pintype "passive"))
    )
    (net (code "228") (name "Net-(PWM3-Pad1)") (class "Default")
      (node (ref "PWM3") (pin "1") (pinfunction "1_1") (pintype "passive"))
      (node (ref "RGB1") (pin "3") (pinfunction "3_3") (pintype "passive"))
    )
    (net (code "229") (name "Net-(PWM4-Pad1)") (class "Default")
      (node (ref "PWM4") (pin "1") (pinfunction "1_1") (pintype "passive"))
      (node (ref "RGB2") (pin "1") (pinfunction "1_1") (pintype "passive"))
    )
    (net (code "230") (name "Net-(PWM5-Pad1)") (class "Default")
      (node (ref "PWM5") (pin "1") (pinfunction "1_1") (pintype "passive"))
      (node (ref "RGB2") (pin "2") (pinfunction "2_2") (pintype "passive"))
    )
    (net (code "231") (name "Net-(PWM6-Pad1)") (class "Default")
      (node (ref "PWM6") (pin "1") (pinfunction "1_1") (pintype "passive"))
      (node (ref "RGB2") (pin "3") (pinfunction "3_3") (pintype "passive"))
    )
    (net (code "232") (name "Net-(PWM7-Pad1)") (class "Default")
      (node (ref "PWM7") (pin "1") (pinfunction "1_1") (pintype "passive"))
      (node (ref "RGB3") (pin "1") (pinfunction "1_1") (pintype "passive"))
    )
    (net (code "233") (name "Net-(PWM8-Pad1)") (class "Default")
      (node (ref "PWM8") (pin "1") (pinfunction "1_1") (pintype "passive"))
      (node (ref "RGB3") (pin "2") (pinfunction "2_2") (pintype "passive"))
    )
    (net (code "234") (name "Net-(PWM9-Pad1)") (class "Default")
      (node (ref "PWM9") (pin "1") (pinfunction "1_1") (pintype "passive"))
      (node (ref "RGB3") (pin "3") (pinfunction "3_3") (pintype "passive"))
    )
    (net (code "235") (name "Net-(PWM10-Pad1)") (class "Default")
      (node (ref "PWM10") (pin "1") (pinfunction "1_1") (pintype "passive"))
      (node (ref "RGB4") (pin "1") (pinfunction "1_1") (pintype "passive"))
    )
    (net (code "236") (name "Net-(PWM11-Pad1)") (class "Default")
      (node (ref "PWM11") (pin "1") (pinfunction "1_1") (pintype "passive"))
      (node (ref "RGB4") (pin "2") (pinfunction "2_2") (pintype "passive"))
    )
    (net (code "237") (name "Net-(PWM12-Pad1)") (class "Default")
      (node (ref "PWM12") (pin "1") (pinfunction "1_1") (pintype "passive"))
      (node (ref "RGB4") (pin "3") (pinfunction "3_3") (pintype "passive"))
    )
    (net (code "238") (name "Net-(PWM13-Pad1)") (class "Default")
      (node (ref "PWM13") (pin "1") (pinfunction "1_1") (pintype "passive"))
      (node (ref "RGB5") (pin "1") (pinfunction "1_1") (pintype "passive"))
    )
    (net (code "239") (name "Net-(PWM14-Pad1)") (class "Default")
      (node (ref "PWM14") (pin "1") (pinfunction "1_1") (pintype "passive"))
      (node (ref "RGB5") (pin "2") (pinfunction "2_2") (pintype "passive"))
    )
    (net (code "240") (name "Net-(PWM15-Pad1)") (class "Default")
      (node (ref "PWM15") (pin "1") (pinfunction "1_1") (pintype "passive"))
      (node (ref "RGB5") (pin "3") (pinfunction "3_3") (pintype "passive"))
    )
    (net (code "241") (name "Net-(PWM16-Pad1)") (class "Default")
      (node (ref "PWM16") (pin "1") (pinfunction "1_1") (pintype "passive"))
      (node (ref "RGB6") (pin "1") (pinfunction "1_1") (pintype "passive"))
    )
    (net (code "242") (name "Net-(PWM17-Pad1)") (class "Default")
      (node (ref "PWM17") (pin "1") (pinfunction "1_1") (pintype "passive"))
      (node (ref "RGB6") (pin "2") (pinfunction "2_2") (pintype "passive"))
    )
    (net (code "243") (name "Net-(PWM18-Pad1)") (class "Default")
      (node (ref "PWM18") (pin "1") (pinfunction "1_1") (pintype "passive"))
      (node (ref "RGB6") (pin "3") (pinfunction "3_3") (pintype "passive"))
    )
    (net (code "244") (name "Net-(Q1-B)") (class "Default")
      (node (ref "Q1") (pin "1") (pinfunction "B_1") (pintype "passive"))
      (node (ref "R3") (pin "1") (pinfunction "1_1") (pintype "passive"))
    )
    (net (code "245") (name "Net-(Q1-C)") (class "Default")
      (node (ref "DS1") (pin "1") (pinfunction "1_1") (pintype "passive"))
      (node (ref "Q1") (pin "3") (pinfunction "C_3") (pintype "passive"))
    )
    (net (code "246") (name "Net-(Q2-B)") (class "Default")
      (node (ref "Q2") (pin "1") (pinfunction "B_1") (pintype "passive"))
      (node (ref "R4") (pin "1") (pinfunction "1_1") (pintype "passive"))
    )
    (net (code "247") (name "Net-(Q2-C)") (class "Default")
      (node (ref "DS2") (pin "1") (pinfunction "1_1") (pintype "passive"))
      (node (ref "Q2") (pin "3") (pinfunction "C_3") (pintype "passive"))
    )
    (net (code "248") (name "Net-(Q3-G)") (class "Default")
      (node (ref "Q3") (pin "1") (pinfunction "G_1") (pintype "passive"))
      (node (ref "R7") (pin "1") (pinfunction "1_1") (pintype "passive"))
      (node (ref "U2") (pin "2") (pinfunction "SE_2") (pintype "passive"))
    )
    (net (code "249") (name "Net-(Q4-B)") (class "Default")
      (node (ref "Q4") (pin "1") (pinfunction "B_1") (pintype "passive"))
      (node (ref "R8") (pin "1") (pinfunction "1_1") (pintype "passive"))
    )
    (net (code "250") (name "Net-(Q4-C)") (class "Default")
      (node (ref "DS3") (pin "1") (pinfunction "1_1") (pintype "passive"))
      (node (ref "Q4") (pin "3") (pinfunction "C_3") (pintype "passive"))
    )
    (net (code "251") (name "Net-(Q5-B)") (class "Default")
      (node (ref "Q5") (pin "1") (pinfunction "B_1") (pintype "passive"))
      (node (ref "R9") (pin "1") (pinfunction "1_1") (pintype "passive"))
    )
    (net (code "252") (name "Net-(Q5-C)") (class "Default")
      (node (ref "DS4") (pin "1") (pinfunction "1_1") (pintype "passive"))
      (node (ref "Q5") (pin "3") (pinfunction "C_3") (pintype "passive"))
    )
    (net (code "253") (name "Net-(Q6-B)") (class "Default")
      (node (ref "Q6") (pin "1") (pinfunction "B_1") (pintype "passive"))
      (node (ref "R32") (pin "2") (pinfunction "2_2") (pintype "passive"))
    )
    (net (code "254") (name "Net-(U2-DRI)") (class "Default")
      (node (ref "C7") (pin "1") (pinfunction "1_1") (pintype "passive"))
      (node (ref "C9") (pin "2") (pinfunction "2_2") (pintype "passive"))
      (node (ref "L") (pin "1") (pinfunction "1_1") (pintype "passive"))
      (node (ref "Relay") (pin "3") (pinfunction "3_3") (pintype "passive"))
      (node (ref "U2") (pin "1") (pinfunction "SC_1") (pintype "passive"))
      (node (ref "U2") (pin "6") (pinfunction "VCC_6") (pintype "passive"))
      (node (ref "U2") (pin "7") (pinfunction "IPK_7") (pintype "passive"))
      (node (ref "U2") (pin "8") (pinfunction "DRI_8") (pintype "passive"))
    )
    (net (code "255") (name "Net-(U2-FB)") (class "Default")
      (node (ref "C1") (pin "1") (pinfunction "1_1") (pintype "passive"))
      (node (ref "R1") (pin "1") (pinfunction "1_1") (pintype "passive"))
      (node (ref "R2") (pin "2") (pinfunction "2_2") (pintype "passive"))
      (node (ref "U2") (pin "5") (pinfunction "FB_5") (pintype "passive"))
    )
    (net (code "256") (name "Net-(U2-TC)") (class "Default")
      (node (ref "C2") (pin "2") (pinfunction "2_2") (pintype "passive"))
      (node (ref "U2") (pin "3") (pinfunction "TC_3") (pintype "passive"))
    )
    (net (code "257") (name "Net-(U6A-PD0-OSC_IN)") (class "Default")
      (node (ref "C11") (pin "2") (pinfunction "2_2") (pintype "passive"))
      (node (ref "R26") (pin "2") (pinfunction "2_2") (pintype "passive"))
      (node (ref "U6") (pin "5") (pinfunction "PD0-OSC_IN_5") (pintype "bidirectional"))
      (node (ref "Y*1") (pin "1") (pinfunction "OSC1_1") (pintype "passive"))
    )
    (net (code "258") (name "Net-(U6A-PD1)") (class "Default")
      (node (ref "C12") (pin "2") (pinfunction "2_2") (pintype "passive"))
      (node (ref "R26") (pin "1") (pinfunction "1_1") (pintype "passive"))
      (node (ref "U6") (pin "6") (pinfunction "PD1_6") (pintype "bidirectional"))
      (node (ref "Y*1") (pin "3") (pinfunction "OSC2_3") (pintype "passive"))
    )
    (net (code "259") (name "V3.3") (class "Default")
      (node (ref "*") (pin "23") (pinfunction "VCC_23") (pintype "passive"))
      (node (ref "BOOT") (pin "1") (pinfunction "1_1") (pintype "passive"))
      (node (ref "BOOT") (pin "2") (pinfunction "2_2") (pintype "passive"))
      (node (ref "C14") (pin "2") (pinfunction "2_2") (pintype "passive"))
      (node (ref "C15") (pin "2") (pinfunction "2_2") (pintype "passive"))
      (node (ref "C16") (pin "2") (pinfunction "2_2") (pintype "passive"))
      (node (ref "C17") (pin "2") (pinfunction "2_2") (pintype "passive"))
      (node (ref "C18") (pin "2") (pinfunction "2_2") (pintype "passive"))
      (node (ref "C19") (pin "2") (pinfunction "2_2") (pintype "passive"))
      (node (ref "C20") (pin "1") (pinfunction "1_1") (pintype "passive"))
      (node (ref "CA7") (pin "1") (pinfunction "1_1") (pintype "passive"))
      (node (ref "CA8") (pin "1") (pinfunction "1_1") (pintype "passive"))
      (node (ref "D3") (pin "2") (pinfunction "K_2") (pintype "passive"))
      (node (ref "GPS") (pin "1") (pinfunction "1_1") (pintype "passive"))
      (node (ref "L3") (pin "1") (pinfunction "A_1") (pintype "passive"))
      (node (ref "PA1") (pin "14") (pinfunction "14_14") (pintype "passive"))
      (node (ref "PA1") (pin "27") (pinfunction "27_27") (pintype "passive"))
      (node (ref "PA2") (pin "14") (pinfunction "14_14") (pintype "passive"))
      (node (ref "PA2") (pin "27") (pinfunction "27_27") (pintype "passive"))
      (node (ref "PA3") (pin "14") (pinfunction "14_14") (pintype "passive"))
      (node (ref "PA3") (pin "27") (pinfunction "27_27") (pintype "passive"))
      (node (ref "R28") (pin "1") (pinfunction "1_1") (pintype "passive"))
      (node (ref "R29") (pin "2") (pinfunction "2_2") (pintype "passive"))
      (node (ref "R40") (pin "2") (pinfunction "2_2") (pintype "passive"))
      (node (ref "R41") (pin "2") (pinfunction "2_2") (pintype "passive"))
      (node (ref "Relay") (pin "1") (pinfunction "+_1") (pintype "passive"))
      (node (ref "SWD") (pin "4") (pinfunction "4_4") (pintype "passive"))
      (node (ref "U6") (pin "1") (pinfunction "VBAT_1") (pintype "power_in"))
      (node (ref "U6") (pin "13") (pinfunction "VDDA_13") (pintype "power_in"))
      (node (ref "U6") (pin "19") (pinfunction "VDD_4_19") (pintype "power_in"))
      (node (ref "U6") (pin "32") (pinfunction "VDD_1_32") (pintype "power_in"))
      (node (ref "U6") (pin "48") (pinfunction "VDD_2_48") (pintype "power_in"))
      (node (ref "U6") (pin "64") (pinfunction "VDD_3_64") (pintype "power_in"))
      (node (ref "U7") (pin "2") (pinfunction "VCC_2") (pintype "passive"))
      (node (ref "UA2") (pin "4") (pinfunction "OUT_4") (pintype "power_in"))
      (node (ref "UART") (pin "4") (pinfunction "4_4") (pintype "passive"))
    )
    (net (code "260") (name "V5") (class "Default")
      (node (ref "C10") (pin "2") (pinfunction "2_2") (pintype "passive"))
      (node (ref "CA4") (pin "1") (pinfunction "1_1") (pintype "passive"))
      (node (ref "CA5") (pin "1") (pinfunction "1_1") (pintype "passive"))
      (node (ref "CA6") (pin "2") (pinfunction "2_2") (pintype "passive"))
      (node (ref "L2") (pin "1") (pinfunction "A_1") (pintype "passive"))
      (node (ref "LA1") (pin "2") (pinfunction "2_2") (pintype "passive"))
      (node (ref "R17") (pin "1") (pinfunction "1_1") (pintype "passive"))
      (node (ref "R18") (pin "1") (pinfunction "1_1") (pintype "passive"))
      (node (ref "R19") (pin "1") (pinfunction "1_1") (pintype "passive"))
      (node (ref "R20") (pin "1") (pinfunction "1_1") (pintype "passive"))
      (node (ref "R21") (pin "1") (pinfunction "1_1") (pintype "passive"))
      (node (ref "R22") (pin "1") (pinfunction "1_1") (pintype "passive"))
      (node (ref "R23") (pin "1") (pinfunction "1_1") (pintype "passive"))
      (node (ref "U4") (pin "31") (pinfunction "BL_31") (pintype "passive"))
      (node (ref "U4") (pin "32") (pinfunction "VDD_32") (pintype "passive"))
      (node (ref "U4") (pin "33") (pinfunction "DIR_33") (pintype "passive"))
      (node (ref "UA") (pin "4") (pinfunction "FB_4") (pintype "input"))
      (node (ref "UA2") (pin "3") (pinfunction "IN_3") (pintype "power_in"))
    )
    (net (code "261") (name "V12") (class "Default")
      (node (ref "CA1") (pin "2") (pinfunction "2_2") (pintype "passive"))
      (node (ref "CA2") (pin "1") (pinfunction "1_1") (pintype "passive"))
      (node (ref "DC1") (pin "1") (pinfunction "1_1") (pintype "passive"))
      (node (ref "L1") (pin "1") (pinfunction "A_1") (pintype "passive"))
      (node (ref "Relay") (pin "2") (pinfunction "2_2") (pintype "passive"))
      (node (ref "UA") (pin "1") (pinfunction "IN_1") (pintype "power_in"))
    )
    (net (code "262") (name "VH") (class "Default")
      (node (ref "C4") (pin "1") (pinfunction "1_1") (pintype "passive"))
      (node (ref "D1") (pin "2") (pinfunction "K_2") (pintype "passive"))
      (node (ref "PA1") (pin "13") (pinfunction "13_13") (pintype "passive"))
      (node (ref "PA1") (pin "16") (pinfunction "16_16") (pintype "passive"))
      (node (ref "PA1") (pin "2") (pinfunction "2_2") (pintype "passive"))
      (node (ref "PA1") (pin "28") (pinfunction "28_28") (pintype "passive"))
      (node (ref "PA2") (pin "13") (pinfunction "13_13") (pintype "passive"))
      (node (ref "PA2") (pin "16") (pinfunction "16_16") (pintype "passive"))
      (node (ref "PA2") (pin "2") (pinfunction "2_2") (pintype "passive"))
      (node (ref "PA2") (pin "28") (pinfunction "28_28") (pintype "passive"))
      (node (ref "PA3") (pin "13") (pinfunction "13_13") (pintype "passive"))
      (node (ref "PA3") (pin "16") (pinfunction "16_16") (pintype "passive"))
      (node (ref "PA3") (pin "2") (pinfunction "2_2") (pintype "passive"))
      (node (ref "PA3") (pin "28") (pinfunction "28_28") (pintype "passive"))
      (node (ref "R14") (pin "2") (pinfunction "2_2") (pintype "passive"))
      (node (ref "R2") (pin "1") (pinfunction "1_1") (pintype "passive"))
    )
    (net (code "263") (name "unconnected-(*-AADET_N-Pad2)") (class "Default")
      (node (ref "*") (pin "2") (pinfunction "AADET_N_2") (pintype "passive"))
    )
    (net (code "264") (name "unconnected-(*-EXTINT0-Pad4)") (class "Default")
      (node (ref "*") (pin "4") (pinfunction "EXTINT0_4") (pintype "passive"))
    )
    (net (code "265") (name "unconnected-(*-GPIO2-Pad5)") (class "Default")
      (node (ref "*") (pin "5") (pinfunction "GPIO2_5") (pintype "passive"))
    )
    (net (code "266") (name "unconnected-(*-RST-Pad1)") (class "Default")
      (node (ref "*") (pin "1") (pinfunction "RST_1") (pintype "passive"))
    )
    (net (code "267") (name "unconnected-(*-RSV-Pad8)") (class "Default")
      (node (ref "*") (pin "8") (pinfunction "RSV_8") (pintype "passive"))
    )
    (net (code "268") (name "unconnected-(*-RX2-Pad7)") (class "Default")
      (node (ref "*") (pin "7") (pinfunction "RX2_7") (pintype "passive"))
    )
    (net (code "269") (name "unconnected-(*-SCL-Pad19)") (class "Default")
      (node (ref "*") (pin "19") (pinfunction "SCL_19") (pintype "passive"))
    )
    (net (code "270") (name "unconnected-(*-SDA-Pad18)") (class "Default")
      (node (ref "*") (pin "18") (pinfunction "SDA_18") (pintype "passive"))
    )
    (net (code "271") (name "unconnected-(*-SPI_CS-Pad17)") (class "Default")
      (node (ref "*") (pin "17") (pinfunction "SPI_CS_17") (pintype "passive"))
    )
    (net (code "272") (name "unconnected-(*-SPI_SCK-Pad16)") (class "Default")
      (node (ref "*") (pin "16") (pinfunction "SPI_SCK_16") (pintype "passive"))
    )
    (net (code "273") (name "unconnected-(*-SPI_SDI-Pad15)") (class "Default")
      (node (ref "*") (pin "15") (pinfunction "SPI_SDI_15") (pintype "passive"))
    )
    (net (code "274") (name "unconnected-(*-SPI_SDO-Pad14)") (class "Default")
      (node (ref "*") (pin "14") (pinfunction "SPI_SDO_14") (pintype "passive"))
    )
    (net (code "275") (name "unconnected-(*-TX2-Pad6)") (class "Default")
      (node (ref "*") (pin "6") (pinfunction "TX2_6") (pintype "passive"))
    )
    (net (code "276") (name "unconnected-(*-V_BCKP-Pad22)") (class "Default")
      (node (ref "*") (pin "22") (pinfunction "V_BCKP_22") (pintype "passive"))
    )
    (net (code "277") (name "unconnected-(N1-Cathode_comma-Pad2)") (class "Default")
      (node (ref "N1") (pin "2") (pinfunction "Cathode_comma_2") (pintype "passive+no_connect"))
    )
    (net (code "278") (name "unconnected-(N1-Cathode_comma-Pad13)") (class "Default")
      (node (ref "N1") (pin "13") (pinfunction "Cathode_comma_13") (pintype "passive+no_connect"))
    )
    (net (code "279") (name "unconnected-(N2-Cathode_comma-Pad2)") (class "Default")
      (node (ref "N2") (pin "2") (pinfunction "Cathode_comma_2") (pintype "passive+no_connect"))
    )
    (net (code "280") (name "unconnected-(N2-Cathode_comma-Pad13)") (class "Default")
      (node (ref "N2") (pin "13") (pinfunction "Cathode_comma_13") (pintype "passive+no_connect"))
    )
    (net (code "281") (name "unconnected-(N3-Cathode_comma-Pad2)") (class "Default")
      (node (ref "N3") (pin "2") (pinfunction "Cathode_comma_2") (pintype "passive+no_connect"))
    )
    (net (code "282") (name "unconnected-(N3-Cathode_comma-Pad13)") (class "Default")
      (node (ref "N3") (pin "13") (pinfunction "Cathode_comma_13") (pintype "passive+no_connect"))
    )
    (net (code "283") (name "unconnected-(N4-Cathode_comma-Pad2)") (class "Default")
      (node (ref "N4") (pin "2") (pinfunction "Cathode_comma_2") (pintype "passive+no_connect"))
    )
    (net (code "284") (name "unconnected-(N4-Cathode_comma-Pad13)") (class "Default")
      (node (ref "N4") (pin "13") (pinfunction "Cathode_comma_13") (pintype "passive+no_connect"))
    )
    (net (code "285") (name "unconnected-(N5-Cathode_comma-Pad2)") (class "Default")
      (node (ref "N5") (pin "2") (pinfunction "Cathode_comma_2") (pintype "passive+no_connect"))
    )
    (net (code "286") (name "unconnected-(N5-Cathode_comma-Pad13)") (class "Default")
      (node (ref "N5") (pin "13") (pinfunction "Cathode_comma_13") (pintype "passive+no_connect"))
    )
    (net (code "287") (name "unconnected-(N6-Cathode_comma-Pad2)") (class "Default")
      (node (ref "N6") (pin "2") (pinfunction "Cathode_comma_2") (pintype "passive+no_connect"))
    )
    (net (code "288") (name "unconnected-(N6-Cathode_comma-Pad13)") (class "Default")
      (node (ref "N6") (pin "13") (pinfunction "Cathode_comma_13") (pintype "passive+no_connect"))
    )
    (net (code "289") (name "unconnected-(OLED-CS-Pad13)") (class "Default")
      (node (ref "OLED") (pin "13") (pinfunction "CS_13") (pintype "passive"))
    )
    (net (code "290") (name "unconnected-(OLED-D2-Pad20)") (class "Default")
      (node (ref "OLED") (pin "20") (pinfunction "D2_20") (pintype "passive"))
    )
    (net (code "291") (name "unconnected-(Relay-Pad4)") (class "Default")
      (node (ref "Relay") (pin "4") (pinfunction "4_4") (pintype "passive"))
    )
    (net (code "292") (name "unconnected-(Relay-Pad5)") (class "Default")
      (node (ref "Relay") (pin "5") (pinfunction "5_5") (pintype "passive"))
    )
    (net (code "293") (name "unconnected-(Relay-Pad6)") (class "Default")
      (node (ref "Relay") (pin "6") (pinfunction "6_6") (pintype "passive"))
    )
    (net (code "294") (name "unconnected-(Relay-Pad7)") (class "Default")
      (node (ref "Relay") (pin "7") (pinfunction "7_7") (pintype "passive"))
    )
    (net (code "295") (name "unconnected-(U4-DOUT1{slash}DIN4(B)-Pad39)") (class "Default")
      (node (ref "U4") (pin "39") (pinfunction "DOUT1/DIN4(B)_39") (pintype "passive+no_connect"))
    )
    (net (code "296") (name "unconnected-(U4-DOUT2{slash}DIN3(B)-Pad38)") (class "Default")
      (node (ref "U4") (pin "38") (pinfunction "DOUT2/DIN3(B)_38") (pintype "passive+no_connect"))
    )
    (net (code "297") (name "unconnected-(U4-DOUT3{slash}DIN2(B)-Pad37)") (class "Default")
      (node (ref "U4") (pin "37") (pinfunction "DOUT3/DIN2(B)_37") (pintype "passive+no_connect"))
    )
    (net (code "298") (name "unconnected-(U4-DOUT4{slash}DIN1(B)-Pad36)") (class "Default")
      (node (ref "U4") (pin "36") (pinfunction "DOUT4/DIN1(B)_36") (pintype "passive+no_connect"))
    )
    (net (code "299") (name "unconnected-(U4-HVOUT61{slash}4-Pad44)") (class "Default")
      (node (ref "U4") (pin "44") (pinfunction "HVOUT61/4_44") (pintype "passive"))
    )
    (net (code "300") (name "unconnected-(U4-HVOUT62{slash}3-Pad43)") (class "Default")
      (node (ref "U4") (pin "43") (pinfunction "HVOUT62/3_43") (pintype "passive"))
    )
    (net (code "301") (name "unconnected-(U4-HVOUT63{slash}2-Pad42)") (class "Default")
      (node (ref "U4") (pin "42") (pinfunction "HVOUT63/2_42") (pintype "passive"))
    )
    (net (code "302") (name "unconnected-(U4-HVOUT64{slash}1-Pad41)") (class "Default")
      (node (ref "U4") (pin "41") (pinfunction "HVOUT64/1_41") (pintype "passive"))
    )
    (net (code "303") (name "unconnected-(U6A-PC8-Pad39)") (class "Default")
      (node (ref "U6") (pin "39") (pinfunction "PC8_39") (pintype "bidirectional"))
    )
    (net (code "304") (name "unconnected-(U7-32kHz-Pad1)") (class "Default")
      (node (ref "U7") (pin "1") (pinfunction "32kHz_1") (pintype "passive"))
    )
  )
)
